# harp_input_expander.net
KiCad netlist of a schematic drawn in EAGLE
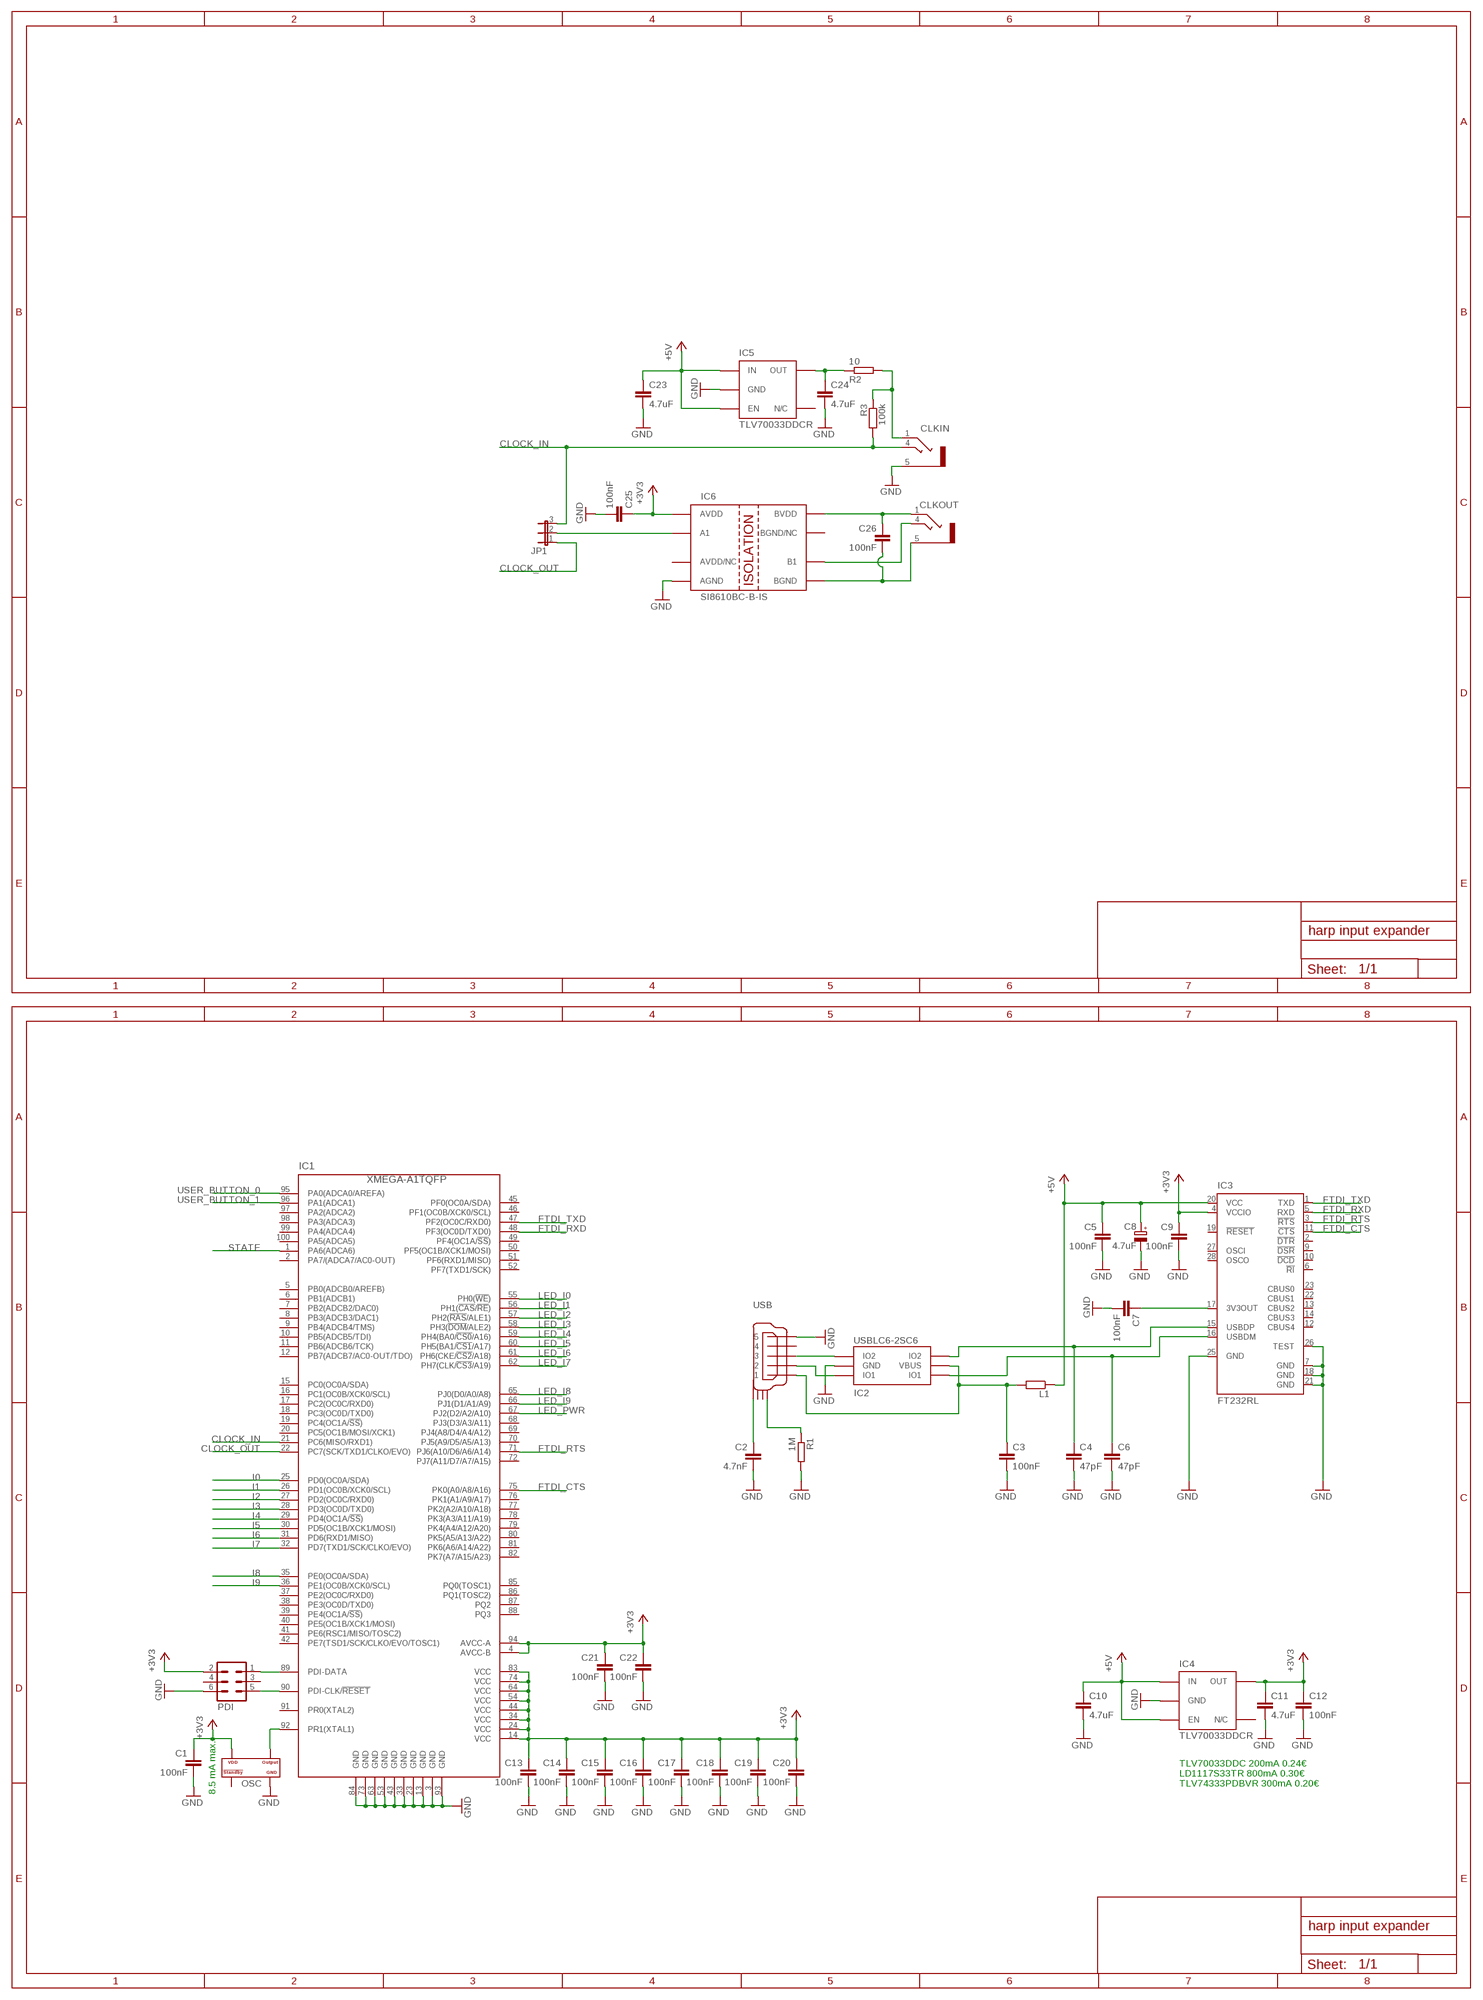
[diagram p0: schematic, sheet 1, part 1 of 2]
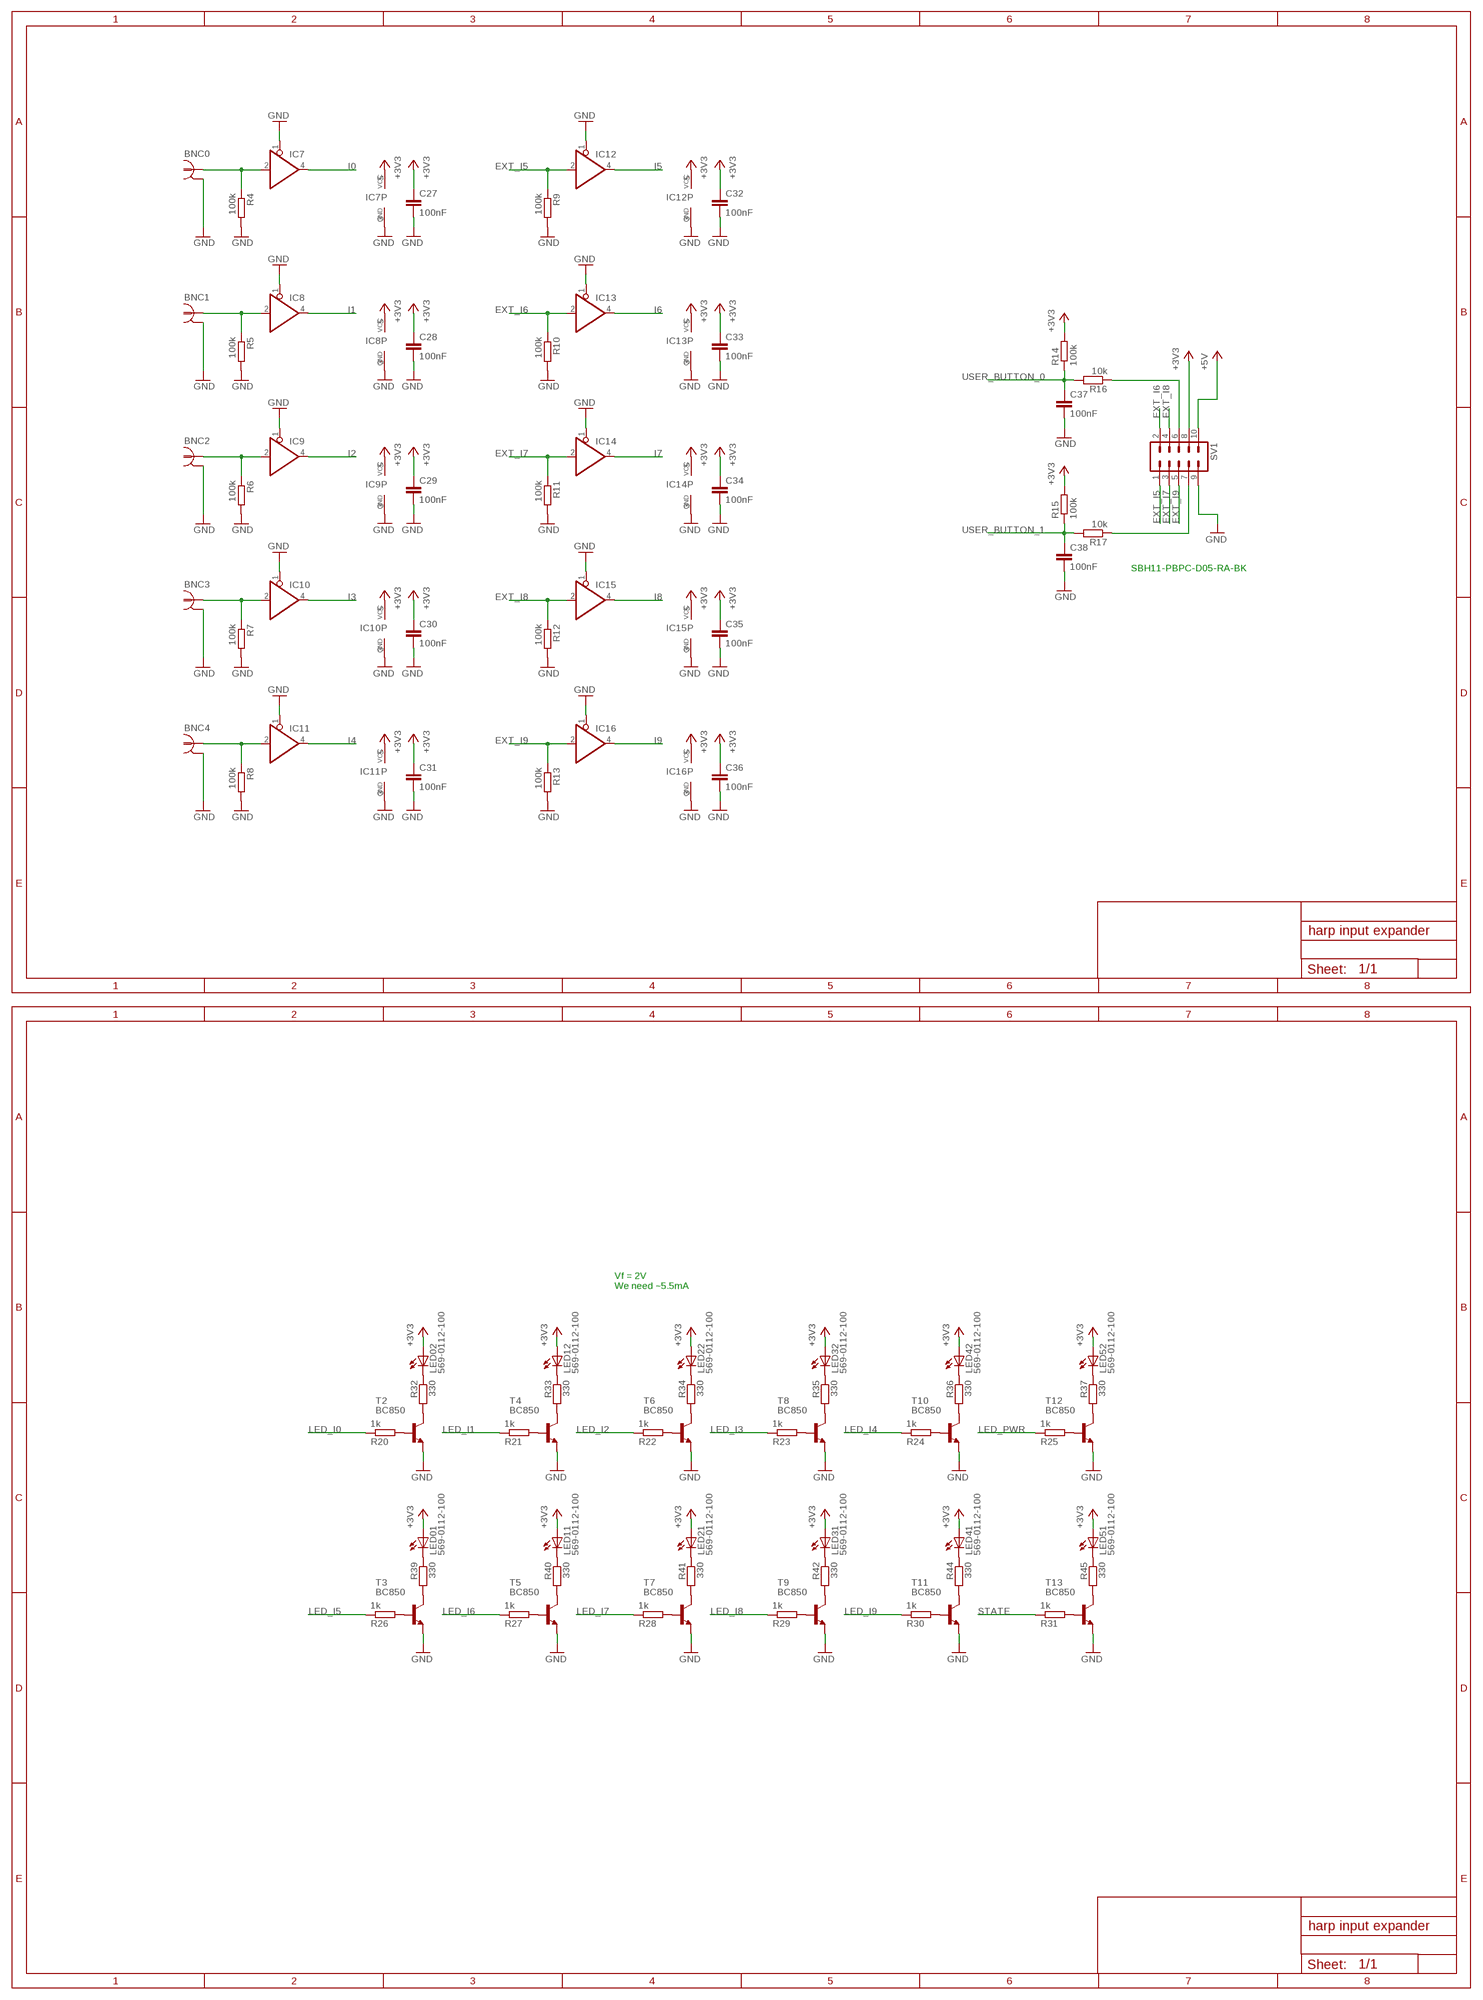
[diagram p1: schematic, sheet 1, part 2 of 2]

(export (version "E")
  (design (tool "Eeschema 10.0.6"))
  (components
    (comp (ref "BNC0")
      (value "BNC_0731000105")
      (footprint "eagle-import:0731000105")
      (libsource (lib "eagle-import") (part "BNC_0731000105"))
    )
    (comp (ref "BNC1")
      (value "BNC_0731000105")
      (footprint "eagle-import:0731000105")
      (libsource (lib "eagle-import") (part "BNC_0731000105"))
    )
    (comp (ref "BNC2")
      (value "BNC_0731000105")
      (footprint "eagle-import:0731000105")
      (libsource (lib "eagle-import") (part "BNC_0731000105"))
    )
    (comp (ref "BNC3")
      (value "BNC_0731000105")
      (footprint "eagle-import:0731000105")
      (libsource (lib "eagle-import") (part "BNC_0731000105"))
    )
    (comp (ref "BNC4")
      (value "BNC_0731000105")
      (footprint "eagle-import:0731000105")
      (libsource (lib "eagle-import") (part "BNC_0731000105"))
    )
    (comp (ref "C1")
      (value "100nF")
      (footprint "eagle-import:C0402")
      (libsource (lib "eagle-import") (part "C-EUC0402"))
    )
    (comp (ref "C2")
      (value "4.7nF")
      (footprint "eagle-import:C0402")
      (libsource (lib "eagle-import") (part "C-EUC0402"))
    )
    (comp (ref "C3")
      (value "100nF")
      (footprint "eagle-import:C0402")
      (libsource (lib "eagle-import") (part "C-EUC0402"))
    )
    (comp (ref "C4")
      (value "47pF")
      (footprint "eagle-import:C0402")
      (libsource (lib "eagle-import") (part "C-EUC0402"))
    )
    (comp (ref "C5")
      (value "100nF")
      (footprint "eagle-import:C0402")
      (libsource (lib "eagle-import") (part "C-EUC0402"))
    )
    (comp (ref "C6")
      (value "47pF")
      (footprint "eagle-import:C0402")
      (libsource (lib "eagle-import") (part "C-EUC0402"))
    )
    (comp (ref "C7")
      (value "100nF")
      (footprint "eagle-import:C0402")
      (libsource (lib "eagle-import") (part "C-EUC0402"))
    )
    (comp (ref "C8")
      (value "4.7uF")
      (footprint "eagle-import:A_3216-18W")
      (libsource (lib "eagle-import") (part "CPOL-EUA/3216-18W"))
    )
    (comp (ref "C9")
      (value "100nF")
      (footprint "eagle-import:C0402")
      (libsource (lib "eagle-import") (part "C-EUC0402"))
    )
    (comp (ref "C10")
      (value "4.7uF")
      (footprint "eagle-import:C0603")
      (libsource (lib "eagle-import") (part "C-EUC0603"))
    )
    (comp (ref "C11")
      (value "4.7uF")
      (footprint "eagle-import:C0603")
      (libsource (lib "eagle-import") (part "C-EUC0603"))
    )
    (comp (ref "C12")
      (value "100nF")
      (footprint "eagle-import:C0402")
      (libsource (lib "eagle-import") (part "C-EUC0402"))
    )
    (comp (ref "C13")
      (value "100nF")
      (footprint "eagle-import:C0402")
      (libsource (lib "eagle-import") (part "C-EUC0402"))
    )
    (comp (ref "C14")
      (value "100nF")
      (footprint "eagle-import:C0402")
      (libsource (lib "eagle-import") (part "C-EUC0402"))
    )
    (comp (ref "C15")
      (value "100nF")
      (footprint "eagle-import:C0402")
      (libsource (lib "eagle-import") (part "C-EUC0402"))
    )
    (comp (ref "C16")
      (value "100nF")
      (footprint "eagle-import:C0402")
      (libsource (lib "eagle-import") (part "C-EUC0402"))
    )
    (comp (ref "C17")
      (value "100nF")
      (footprint "eagle-import:C0402")
      (libsource (lib "eagle-import") (part "C-EUC0402"))
    )
    (comp (ref "C18")
      (value "100nF")
      (footprint "eagle-import:C0402")
      (libsource (lib "eagle-import") (part "C-EUC0402"))
    )
    (comp (ref "C19")
      (value "100nF")
      (footprint "eagle-import:C0402")
      (libsource (lib "eagle-import") (part "C-EUC0402"))
    )
    (comp (ref "C20")
      (value "100nF")
      (footprint "eagle-import:C0402")
      (libsource (lib "eagle-import") (part "C-EUC0402"))
    )
    (comp (ref "C21")
      (value "100nF")
      (footprint "eagle-import:C0402")
      (libsource (lib "eagle-import") (part "C-EUC0402"))
    )
    (comp (ref "C22")
      (value "100nF")
      (footprint "eagle-import:C0402")
      (libsource (lib "eagle-import") (part "C-EUC0402"))
    )
    (comp (ref "C23")
      (value "4.7uF")
      (footprint "eagle-import:C0603")
      (libsource (lib "eagle-import") (part "C-EUC0603"))
    )
    (comp (ref "C24")
      (value "4.7uF")
      (footprint "eagle-import:C0603")
      (libsource (lib "eagle-import") (part "C-EUC0603"))
    )
    (comp (ref "C25")
      (value "100nF")
      (footprint "eagle-import:C0402")
      (libsource (lib "eagle-import") (part "C-EUC0402"))
    )
    (comp (ref "C26")
      (value "100nF")
      (footprint "eagle-import:C0402")
      (libsource (lib "eagle-import") (part "C-EUC0402"))
    )
    (comp (ref "C27")
      (value "100nF")
      (footprint "eagle-import:C0402")
      (libsource (lib "eagle-import") (part "C-EUC0402"))
    )
    (comp (ref "C28")
      (value "100nF")
      (footprint "eagle-import:C0402")
      (libsource (lib "eagle-import") (part "C-EUC0402"))
    )
    (comp (ref "C29")
      (value "100nF")
      (footprint "eagle-import:C0402")
      (libsource (lib "eagle-import") (part "C-EUC0402"))
    )
    (comp (ref "C30")
      (value "100nF")
      (footprint "eagle-import:C0402")
      (libsource (lib "eagle-import") (part "C-EUC0402"))
    )
    (comp (ref "C31")
      (value "100nF")
      (footprint "eagle-import:C0402")
      (libsource (lib "eagle-import") (part "C-EUC0402"))
    )
    (comp (ref "C32")
      (value "100nF")
      (footprint "eagle-import:C0402")
      (libsource (lib "eagle-import") (part "C-EUC0402"))
    )
    (comp (ref "C33")
      (value "100nF")
      (footprint "eagle-import:C0402")
      (libsource (lib "eagle-import") (part "C-EUC0402"))
    )
    (comp (ref "C34")
      (value "100nF")
      (footprint "eagle-import:C0402")
      (libsource (lib "eagle-import") (part "C-EUC0402"))
    )
    (comp (ref "C35")
      (value "100nF")
      (footprint "eagle-import:C0402")
      (libsource (lib "eagle-import") (part "C-EUC0402"))
    )
    (comp (ref "C36")
      (value "100nF")
      (footprint "eagle-import:C0402")
      (libsource (lib "eagle-import") (part "C-EUC0402"))
    )
    (comp (ref "C37")
      (value "100nF")
      (footprint "eagle-import:C0402")
      (libsource (lib "eagle-import") (part "C-EUC0402"))
    )
    (comp (ref "C38")
      (value "100nF")
      (footprint "eagle-import:C0402")
      (libsource (lib "eagle-import") (part "C-EUC0402"))
    )
    (comp (ref "CLKIN")
      (value "STEREO_JACK")
      (footprint "eagle-import:35RASMT2BHNTRX")
      (libsource (lib "eagle-import") (part "STEREO_JACK"))
    )
    (comp (ref "CLKOUT")
      (value "STEREO_JACK")
      (footprint "eagle-import:35RASMT2BHNTRX")
      (libsource (lib "eagle-import") (part "STEREO_JACK"))
    )
    (comp (ref "IC1")
      (value "XMEGA-A1TQFP")
      (footprint "eagle-import:TQFP100")
      (libsource (lib "eagle-import") (part "XMEGA-A1TQFP"))
    )
    (comp (ref "IC2")
      (value "USBLC6-2SC6")
      (footprint "eagle-import:SOT23-6L")
      (libsource (lib "eagle-import") (part "USBLC6-2"))
    )
    (comp (ref "IC3")
      (value "FT232RL")
      (footprint "eagle-import:SSOP28")
      (libsource (lib "eagle-import") (part "FT232RL"))
    )
    (comp (ref "IC4")
      (value "TLV70033DDCR")
      (footprint "eagle-import:TSOT23-5")
      (libsource (lib "eagle-import") (part "TLV700XX"))
    )
    (comp (ref "IC5")
      (value "TLV70033DDCR")
      (footprint "eagle-import:TSOT23-5")
      (libsource (lib "eagle-import") (part "TLV700XX"))
    )
    (comp (ref "IC6")
      (value "SI8610BC-B-IS")
      (footprint "eagle-import:SO-08")
      (libsource (lib "eagle-import") (part "SI8610"))
    )
    (comp (ref "IC7")
      (value "74AHC1G125DBV")
      (footprint "eagle-import:SOT23-5")
      (libsource (lib "eagle-import") (part "741G125DBVAHC"))
    )
    (comp (ref "IC8")
      (value "74AHC1G125DBV")
      (footprint "eagle-import:SOT23-5")
      (libsource (lib "eagle-import") (part "741G125DBVAHC"))
    )
    (comp (ref "IC9")
      (value "74AHC1G125DBV")
      (footprint "eagle-import:SOT23-5")
      (libsource (lib "eagle-import") (part "741G125DBVAHC"))
    )
    (comp (ref "IC10")
      (value "74AHC1G125DBV")
      (footprint "eagle-import:SOT23-5")
      (libsource (lib "eagle-import") (part "741G125DBVAHC"))
    )
    (comp (ref "IC11")
      (value "74AHC1G125DBV")
      (footprint "eagle-import:SOT23-5")
      (libsource (lib "eagle-import") (part "741G125DBVAHC"))
    )
    (comp (ref "IC12")
      (value "74AHC1G125DBV")
      (footprint "eagle-import:SOT23-5")
      (libsource (lib "eagle-import") (part "741G125DBVAHC"))
    )
    (comp (ref "IC13")
      (value "74AHC1G125DBV")
      (footprint "eagle-import:SOT23-5")
      (libsource (lib "eagle-import") (part "741G125DBVAHC"))
    )
    (comp (ref "IC14")
      (value "74AHC1G125DBV")
      (footprint "eagle-import:SOT23-5")
      (libsource (lib "eagle-import") (part "741G125DBVAHC"))
    )
    (comp (ref "IC15")
      (value "74AHC1G125DBV")
      (footprint "eagle-import:SOT23-5")
      (libsource (lib "eagle-import") (part "741G125DBVAHC"))
    )
    (comp (ref "IC16")
      (value "74AHC1G125DBV")
      (footprint "eagle-import:SOT23-5")
      (libsource (lib "eagle-import") (part "741G125DBVAHC"))
    )
    (comp (ref "JP1")
      (value "JP2E")
      (footprint "eagle-import:JP2")
      (libsource (lib "eagle-import") (part "JP2E"))
    )
    (comp (ref "L1")
      (value "???")
      (footprint "eagle-import:R0805")
      (libsource (lib "eagle-import") (part "R-EU_R0805"))
    )
    (comp (ref "LED0")
      (value "569-0112-100")
      (footprint "eagle-import:569-011X-X00_LED_ARRAY")
      (libsource (lib "eagle-import") (part "LED_2X_VERTICAL"))
    )
    (comp (ref "LED1")
      (value "569-0112-100")
      (footprint "eagle-import:569-011X-X00_LED_ARRAY")
      (libsource (lib "eagle-import") (part "LED_2X_VERTICAL"))
    )
    (comp (ref "LED2")
      (value "569-0112-100")
      (footprint "eagle-import:569-011X-X00_LED_ARRAY")
      (libsource (lib "eagle-import") (part "LED_2X_VERTICAL"))
    )
    (comp (ref "LED3")
      (value "569-0112-100")
      (footprint "eagle-import:569-011X-X00_LED_ARRAY")
      (libsource (lib "eagle-import") (part "LED_2X_VERTICAL"))
    )
    (comp (ref "LED4")
      (value "569-0112-100")
      (footprint "eagle-import:569-011X-X00_LED_ARRAY")
      (libsource (lib "eagle-import") (part "LED_2X_VERTICAL"))
    )
    (comp (ref "LED5")
      (value "569-0112-100")
      (footprint "eagle-import:569-011X-X00_LED_ARRAY")
      (libsource (lib "eagle-import") (part "LED_2X_VERTICAL"))
    )
    (comp (ref "OSC")
      (value "OSCILLATOR")
      (footprint "eagle-import:OSCILLATOR_3.2X2.5")
      (libsource (lib "eagle-import") (part "OSCILLATOR"))
    )
    (comp (ref "PDI")
      (value "MA03-2")
      (footprint "eagle-import:MA03-2")
      (libsource (lib "eagle-import") (part "MA03-2"))
    )
    (comp (ref "R1")
      (value "1M")
      (footprint "eagle-import:R0402")
      (libsource (lib "eagle-import") (part "R-EU_R0402"))
    )
    (comp (ref "R2")
      (value "10")
      (footprint "eagle-import:R0402")
      (libsource (lib "eagle-import") (part "R-EU_R0402"))
    )
    (comp (ref "R3")
      (value "100k")
      (footprint "eagle-import:R0402")
      (libsource (lib "eagle-import") (part "R-EU_R0402"))
    )
    (comp (ref "R4")
      (value "100k")
      (footprint "eagle-import:R0402")
      (libsource (lib "eagle-import") (part "R-EU_R0402"))
    )
    (comp (ref "R5")
      (value "100k")
      (footprint "eagle-import:R0402")
      (libsource (lib "eagle-import") (part "R-EU_R0402"))
    )
    (comp (ref "R6")
      (value "100k")
      (footprint "eagle-import:R0402")
      (libsource (lib "eagle-import") (part "R-EU_R0402"))
    )
    (comp (ref "R7")
      (value "100k")
      (footprint "eagle-import:R0402")
      (libsource (lib "eagle-import") (part "R-EU_R0402"))
    )
    (comp (ref "R8")
      (value "100k")
      (footprint "eagle-import:R0402")
      (libsource (lib "eagle-import") (part "R-EU_R0402"))
    )
    (comp (ref "R9")
      (value "100k")
      (footprint "eagle-import:R0402")
      (libsource (lib "eagle-import") (part "R-EU_R0402"))
    )
    (comp (ref "R10")
      (value "100k")
      (footprint "eagle-import:R0402")
      (libsource (lib "eagle-import") (part "R-EU_R0402"))
    )
    (comp (ref "R11")
      (value "100k")
      (footprint "eagle-import:R0402")
      (libsource (lib "eagle-import") (part "R-EU_R0402"))
    )
    (comp (ref "R12")
      (value "100k")
      (footprint "eagle-import:R0402")
      (libsource (lib "eagle-import") (part "R-EU_R0402"))
    )
    (comp (ref "R13")
      (value "100k")
      (footprint "eagle-import:R0402")
      (libsource (lib "eagle-import") (part "R-EU_R0402"))
    )
    (comp (ref "R14")
      (value "100k")
      (footprint "eagle-import:R0402")
      (libsource (lib "eagle-import") (part "R-EU_R0402"))
    )
    (comp (ref "R15")
      (value "100k")
      (footprint "eagle-import:R0402")
      (libsource (lib "eagle-import") (part "R-EU_R0402"))
    )
    (comp (ref "R16")
      (value "10k")
      (footprint "eagle-import:R0402")
      (libsource (lib "eagle-import") (part "R-EU_R0402"))
    )
    (comp (ref "R17")
      (value "10k")
      (footprint "eagle-import:R0402")
      (libsource (lib "eagle-import") (part "R-EU_R0402"))
    )
    (comp (ref "R20")
      (value "1k")
      (footprint "eagle-import:R0402")
      (libsource (lib "eagle-import") (part "R-EU_R0402"))
    )
    (comp (ref "R21")
      (value "1k")
      (footprint "eagle-import:R0402")
      (libsource (lib "eagle-import") (part "R-EU_R0402"))
    )
    (comp (ref "R22")
      (value "1k")
      (footprint "eagle-import:R0402")
      (libsource (lib "eagle-import") (part "R-EU_R0402"))
    )
    (comp (ref "R23")
      (value "1k")
      (footprint "eagle-import:R0402")
      (libsource (lib "eagle-import") (part "R-EU_R0402"))
    )
    (comp (ref "R24")
      (value "1k")
      (footprint "eagle-import:R0402")
      (libsource (lib "eagle-import") (part "R-EU_R0402"))
    )
    (comp (ref "R25")
      (value "1k")
      (footprint "eagle-import:R0402")
      (libsource (lib "eagle-import") (part "R-EU_R0402"))
    )
    (comp (ref "R26")
      (value "1k")
      (footprint "eagle-import:R0402")
      (libsource (lib "eagle-import") (part "R-EU_R0402"))
    )
    (comp (ref "R27")
      (value "1k")
      (footprint "eagle-import:R0402")
      (libsource (lib "eagle-import") (part "R-EU_R0402"))
    )
    (comp (ref "R28")
      (value "1k")
      (footprint "eagle-import:R0402")
      (libsource (lib "eagle-import") (part "R-EU_R0402"))
    )
    (comp (ref "R29")
      (value "1k")
      (footprint "eagle-import:R0402")
      (libsource (lib "eagle-import") (part "R-EU_R0402"))
    )
    (comp (ref "R30")
      (value "1k")
      (footprint "eagle-import:R0402")
      (libsource (lib "eagle-import") (part "R-EU_R0402"))
    )
    (comp (ref "R31")
      (value "1k")
      (footprint "eagle-import:R0402")
      (libsource (lib "eagle-import") (part "R-EU_R0402"))
    )
    (comp (ref "R32")
      (value "330")
      (footprint "eagle-import:R0402")
      (libsource (lib "eagle-import") (part "R-EU_R0402"))
    )
    (comp (ref "R33")
      (value "330")
      (footprint "eagle-import:R0402")
      (libsource (lib "eagle-import") (part "R-EU_R0402"))
    )
    (comp (ref "R34")
      (value "330")
      (footprint "eagle-import:R0402")
      (libsource (lib "eagle-import") (part "R-EU_R0402"))
    )
    (comp (ref "R35")
      (value "330")
      (footprint "eagle-import:R0402")
      (libsource (lib "eagle-import") (part "R-EU_R0402"))
    )
    (comp (ref "R36")
      (value "330")
      (footprint "eagle-import:R0402")
      (libsource (lib "eagle-import") (part "R-EU_R0402"))
    )
    (comp (ref "R37")
      (value "330")
      (footprint "eagle-import:R0402")
      (libsource (lib "eagle-import") (part "R-EU_R0402"))
    )
    (comp (ref "R39")
      (value "330")
      (footprint "eagle-import:R0402")
      (libsource (lib "eagle-import") (part "R-EU_R0402"))
    )
    (comp (ref "R40")
      (value "330")
      (footprint "eagle-import:R0402")
      (libsource (lib "eagle-import") (part "R-EU_R0402"))
    )
    (comp (ref "R41")
      (value "330")
      (footprint "eagle-import:R0402")
      (libsource (lib "eagle-import") (part "R-EU_R0402"))
    )
    (comp (ref "R42")
      (value "330")
      (footprint "eagle-import:R0402")
      (libsource (lib "eagle-import") (part "R-EU_R0402"))
    )
    (comp (ref "R44")
      (value "330")
      (footprint "eagle-import:R0402")
      (libsource (lib "eagle-import") (part "R-EU_R0402"))
    )
    (comp (ref "R45")
      (value "330")
      (footprint "eagle-import:R0402")
      (libsource (lib "eagle-import") (part "R-EU_R0402"))
    )
    (comp (ref "SV1")
      (value "ML10L")
      (footprint "eagle-import:ML10L")
      (libsource (lib "eagle-import") (part "ML10L"))
    )
    (comp (ref "T2")
      (value "BC850")
      (footprint "eagle-import:SOT23")
      (libsource (lib "eagle-import") (part "BC850"))
    )
    (comp (ref "T3")
      (value "BC850")
      (footprint "eagle-import:SOT23")
      (libsource (lib "eagle-import") (part "BC850"))
    )
    (comp (ref "T4")
      (value "BC850")
      (footprint "eagle-import:SOT23")
      (libsource (lib "eagle-import") (part "BC850"))
    )
    (comp (ref "T5")
      (value "BC850")
      (footprint "eagle-import:SOT23")
      (libsource (lib "eagle-import") (part "BC850"))
    )
    (comp (ref "T6")
      (value "BC850")
      (footprint "eagle-import:SOT23")
      (libsource (lib "eagle-import") (part "BC850"))
    )
    (comp (ref "T7")
      (value "BC850")
      (footprint "eagle-import:SOT23")
      (libsource (lib "eagle-import") (part "BC850"))
    )
    (comp (ref "T8")
      (value "BC850")
      (footprint "eagle-import:SOT23")
      (libsource (lib "eagle-import") (part "BC850"))
    )
    (comp (ref "T9")
      (value "BC850")
      (footprint "eagle-import:SOT23")
      (libsource (lib "eagle-import") (part "BC850"))
    )
    (comp (ref "T10")
      (value "BC850")
      (footprint "eagle-import:SOT23")
      (libsource (lib "eagle-import") (part "BC850"))
    )
    (comp (ref "T11")
      (value "BC850")
      (footprint "eagle-import:SOT23")
      (libsource (lib "eagle-import") (part "BC850"))
    )
    (comp (ref "T12")
      (value "BC850")
      (footprint "eagle-import:SOT23")
      (libsource (lib "eagle-import") (part "BC850"))
    )
    (comp (ref "T13")
      (value "BC850")
      (footprint "eagle-import:SOT23")
      (libsource (lib "eagle-import") (part "BC850"))
    )
    (comp (ref "USB")
      (value "USB_MINI_B")
      (footprint "eagle-import:240-0002-1")
      (libsource (lib "eagle-import") (part "USB_MINI_B"))
    )
  )
  (nets
    (net (code "1") (name "+3V3") (class "Default")
      (node (ref "C1") (pin "1") (pinfunction "1_1") (pintype "passive"))
      (node (ref "C11") (pin "1") (pinfunction "1_1") (pintype "passive"))
      (node (ref "C12") (pin "1") (pinfunction "1_1") (pintype "passive"))
      (node (ref "C13") (pin "1") (pinfunction "1_1") (pintype "passive"))
      (node (ref "C14") (pin "1") (pinfunction "1_1") (pintype "passive"))
      (node (ref "C15") (pin "1") (pinfunction "1_1") (pintype "passive"))
      (node (ref "C16") (pin "1") (pinfunction "1_1") (pintype "passive"))
      (node (ref "C17") (pin "1") (pinfunction "1_1") (pintype "passive"))
      (node (ref "C18") (pin "1") (pinfunction "1_1") (pintype "passive"))
      (node (ref "C19") (pin "1") (pinfunction "1_1") (pintype "passive"))
      (node (ref "C20") (pin "1") (pinfunction "1_1") (pintype "passive"))
      (node (ref "C21") (pin "1") (pinfunction "1_1") (pintype "passive"))
      (node (ref "C22") (pin "1") (pinfunction "1_1") (pintype "passive"))
      (node (ref "C25") (pin "1") (pinfunction "1_1") (pintype "passive"))
      (node (ref "C27") (pin "1") (pinfunction "1_1") (pintype "passive"))
      (node (ref "C28") (pin "1") (pinfunction "1_1") (pintype "passive"))
      (node (ref "C29") (pin "1") (pinfunction "1_1") (pintype "passive"))
      (node (ref "C30") (pin "1") (pinfunction "1_1") (pintype "passive"))
      (node (ref "C31") (pin "1") (pinfunction "1_1") (pintype "passive"))
      (node (ref "C32") (pin "1") (pinfunction "1_1") (pintype "passive"))
      (node (ref "C33") (pin "1") (pinfunction "1_1") (pintype "passive"))
      (node (ref "C34") (pin "1") (pinfunction "1_1") (pintype "passive"))
      (node (ref "C35") (pin "1") (pinfunction "1_1") (pintype "passive"))
      (node (ref "C36") (pin "1") (pinfunction "1_1") (pintype "passive"))
      (node (ref "C9") (pin "1") (pinfunction "1_1") (pintype "passive"))
      (node (ref "IC1") (pin "14") (pinfunction "VCC_14") (pintype "power_in"))
      (node (ref "IC1") (pin "24") (pinfunction "VCC_24") (pintype "power_in"))
      (node (ref "IC1") (pin "34") (pinfunction "VCC_34") (pintype "power_in"))
      (node (ref "IC1") (pin "4") (pinfunction "AVCC-B_4") (pintype "power_in"))
      (node (ref "IC1") (pin "44") (pinfunction "VCC_44") (pintype "power_in"))
      (node (ref "IC1") (pin "54") (pinfunction "VCC_54") (pintype "power_in"))
      (node (ref "IC1") (pin "64") (pinfunction "VCC_64") (pintype "power_in"))
      (node (ref "IC1") (pin "74") (pinfunction "VCC_74") (pintype "power_in"))
      (node (ref "IC1") (pin "83") (pinfunction "VCC_83") (pintype "power_in"))
      (node (ref "IC1") (pin "94") (pinfunction "AVCC-A_94") (pintype "power_in"))
      (node (ref "IC10") (pin "5") (pinfunction "VCC_5") (pintype "power_in"))
      (node (ref "IC11") (pin "5") (pinfunction "VCC_5") (pintype "power_in"))
      (node (ref "IC12") (pin "5") (pinfunction "VCC_5") (pintype "power_in"))
      (node (ref "IC13") (pin "5") (pinfunction "VCC_5") (pintype "power_in"))
      (node (ref "IC14") (pin "5") (pinfunction "VCC_5") (pintype "power_in"))
      (node (ref "IC15") (pin "5") (pinfunction "VCC_5") (pintype "power_in"))
      (node (ref "IC16") (pin "5") (pinfunction "VCC_5") (pintype "power_in"))
      (node (ref "IC3") (pin "4") (pinfunction "VCCIO_4") (pintype "power_in"))
      (node (ref "IC4") (pin "5") (pinfunction "OUT_5") (pintype "bidirectional"))
      (node (ref "IC6") (pin "1") (pinfunction "AVDD_1") (pintype "bidirectional"))
      (node (ref "IC7") (pin "5") (pinfunction "VCC_5") (pintype "power_in"))
      (node (ref "IC8") (pin "5") (pinfunction "VCC_5") (pintype "power_in"))
      (node (ref "IC9") (pin "5") (pinfunction "VCC_5") (pintype "power_in"))
      (node (ref "LED0") (pin "A1") (pinfunction "A_A1") (pintype "passive"))
      (node (ref "LED0") (pin "A2") (pinfunction "A_A2") (pintype "passive"))
      (node (ref "LED1") (pin "A1") (pinfunction "A_A1") (pintype "passive"))
      (node (ref "LED1") (pin "A2") (pinfunction "A_A2") (pintype "passive"))
      (node (ref "LED2") (pin "A1") (pinfunction "A_A1") (pintype "passive"))
      (node (ref "LED2") (pin "A2") (pinfunction "A_A2") (pintype "passive"))
      (node (ref "LED3") (pin "A1") (pinfunction "A_A1") (pintype "passive"))
      (node (ref "LED3") (pin "A2") (pinfunction "A_A2") (pintype "passive"))
      (node (ref "LED4") (pin "A1") (pinfunction "A_A1") (pintype "passive"))
      (node (ref "LED4") (pin "A2") (pinfunction "A_A2") (pintype "passive"))
      (node (ref "LED5") (pin "A1") (pinfunction "A_A1") (pintype "passive"))
      (node (ref "LED5") (pin "A2") (pinfunction "A_A2") (pintype "passive"))
      (node (ref "OSC") (pin "P$4") (pinfunction "VDD_P$4") (pintype "passive"))
      (node (ref "PDI") (pin "2") (pinfunction "2_2") (pintype "passive"))
      (node (ref "R14") (pin "2") (pinfunction "2_2") (pintype "passive"))
      (node (ref "R15") (pin "2") (pinfunction "2_2") (pintype "passive"))
      (node (ref "SV1") (pin "8") (pinfunction "8_8") (pintype "passive"))
    )
    (net (code "2") (name "+5V") (class "Default")
      (node (ref "C10") (pin "1") (pinfunction "1_1") (pintype "passive"))
      (node (ref "C23") (pin "1") (pinfunction "1_1") (pintype "passive"))
      (node (ref "C5") (pin "1") (pinfunction "1_1") (pintype "passive"))
      (node (ref "C8") (pin "+") (pinfunction "+_+") (pintype "passive"))
      (node (ref "IC3") (pin "20") (pinfunction "VCC_20") (pintype "power_in"))
      (node (ref "IC4") (pin "1") (pinfunction "IN_1") (pintype "bidirectional"))
      (node (ref "IC4") (pin "3") (pinfunction "EN_3") (pintype "bidirectional"))
      (node (ref "IC5") (pin "1") (pinfunction "IN_1") (pintype "bidirectional"))
      (node (ref "IC5") (pin "3") (pinfunction "EN_3") (pintype "bidirectional"))
      (node (ref "L1") (pin "1") (pinfunction "1_1") (pintype "passive"))
      (node (ref "SV1") (pin "10") (pinfunction "10_10") (pintype "passive"))
    )
    (net (code "3") (name "/CLOCK_IN") (class "Default")
      (node (ref "CLKIN") (pin "4") (pinfunction "4_4") (pintype "passive"))
      (node (ref "IC1") (pin "21") (pinfunction "PC6(MISO/RXD1)_21") (pintype "bidirectional"))
      (node (ref "JP1") (pin "3") (pinfunction "3_3") (pintype "passive"))
      (node (ref "R3") (pin "2") (pinfunction "2_2") (pintype "passive"))
    )
    (net (code "4") (name "/CLOCK_OUT") (class "Default")
      (node (ref "IC1") (pin "22") (pinfunction "PC7(SCK/TXD1/CLKO/EVO)_22") (pintype "bidirectional"))
      (node (ref "JP1") (pin "1") (pinfunction "1_1") (pintype "passive"))
    )
    (net (code "5") (name "/EXT_I5") (class "Default")
      (node (ref "IC12") (pin "2") (pinfunction "I_2") (pintype "input"))
      (node (ref "R9") (pin "1") (pinfunction "1_1") (pintype "passive"))
      (node (ref "SV1") (pin "1") (pinfunction "1_1") (pintype "passive"))
    )
    (net (code "6") (name "/EXT_I6") (class "Default")
      (node (ref "IC13") (pin "2") (pinfunction "I_2") (pintype "input"))
      (node (ref "R10") (pin "1") (pinfunction "1_1") (pintype "passive"))
      (node (ref "SV1") (pin "2") (pinfunction "2_2") (pintype "passive"))
    )
    (net (code "7") (name "/EXT_I7") (class "Default")
      (node (ref "IC14") (pin "2") (pinfunction "I_2") (pintype "input"))
      (node (ref "R11") (pin "1") (pinfunction "1_1") (pintype "passive"))
      (node (ref "SV1") (pin "3") (pinfunction "3_3") (pintype "passive"))
    )
    (net (code "8") (name "/EXT_I8") (class "Default")
      (node (ref "IC15") (pin "2") (pinfunction "I_2") (pintype "input"))
      (node (ref "R12") (pin "1") (pinfunction "1_1") (pintype "passive"))
      (node (ref "SV1") (pin "4") (pinfunction "4_4") (pintype "passive"))
    )
    (net (code "9") (name "/EXT_I9") (class "Default")
      (node (ref "IC16") (pin "2") (pinfunction "I_2") (pintype "input"))
      (node (ref "R13") (pin "1") (pinfunction "1_1") (pintype "passive"))
      (node (ref "SV1") (pin "5") (pinfunction "5_5") (pintype "passive"))
    )
    (net (code "10") (name "/FTDI_CTS") (class "Default")
      (node (ref "IC1") (pin "75") (pinfunction "PK0(A0/A8/A16)_75") (pintype "bidirectional"))
      (node (ref "IC3") (pin "11") (pinfunction "~{CTS}_11") (pintype "input"))
    )
    (net (code "11") (name "/FTDI_RTS") (class "Default")
      (node (ref "IC1") (pin "71") (pinfunction "PJ6(A10/D6/A6/A14)_71") (pintype "bidirectional"))
      (node (ref "IC3") (pin "3") (pinfunction "~{RTS}_3") (pintype "output"))
    )
    (net (code "12") (name "/FTDI_RXD") (class "Default")
      (node (ref "IC1") (pin "48") (pinfunction "PF3(OC0D/TXD0)_48") (pintype "bidirectional"))
      (node (ref "IC3") (pin "5") (pinfunction "RXD_5") (pintype "input"))
    )
    (net (code "13") (name "/FTDI_TXD") (class "Default")
      (node (ref "IC1") (pin "47") (pinfunction "PF2(OC0C/RXD0)_47") (pintype "bidirectional"))
      (node (ref "IC3") (pin "1") (pinfunction "TXD_1") (pintype "output"))
    )
    (net (code "14") (name "/I0") (class "Default")
      (node (ref "IC1") (pin "25") (pinfunction "PD0(OC0A/SDA)_25") (pintype "bidirectional"))
      (node (ref "IC7") (pin "4") (pinfunction "O_4") (pintype "tri_state"))
    )
    (net (code "15") (name "/I1") (class "Default")
      (node (ref "IC1") (pin "26") (pinfunction "PD1(OC0B/XCK0/SCL)_26") (pintype "bidirectional"))
      (node (ref "IC8") (pin "4") (pinfunction "O_4") (pintype "tri_state"))
    )
    (net (code "16") (name "/I2") (class "Default")
      (node (ref "IC1") (pin "27") (pinfunction "PD2(OC0C/RXD0)_27") (pintype "bidirectional"))
      (node (ref "IC9") (pin "4") (pinfunction "O_4") (pintype "tri_state"))
    )
    (net (code "17") (name "/I3") (class "Default")
      (node (ref "IC1") (pin "28") (pinfunction "PD3(OC0D/TXD0)_28") (pintype "bidirectional"))
      (node (ref "IC10") (pin "4") (pinfunction "O_4") (pintype "tri_state"))
    )
    (net (code "18") (name "/I4") (class "Default")
      (node (ref "IC1") (pin "29") (pinfunction "PD4(OC1A/~{SS})_29") (pintype "bidirectional"))
      (node (ref "IC11") (pin "4") (pinfunction "O_4") (pintype "tri_state"))
    )
    (net (code "19") (name "/I5") (class "Default")
      (node (ref "IC1") (pin "30") (pinfunction "PD5(OC1B/XCK1/MOSI)_30") (pintype "bidirectional"))
      (node (ref "IC12") (pin "4") (pinfunction "O_4") (pintype "tri_state"))
    )
    (net (code "20") (name "/I6") (class "Default")
      (node (ref "IC1") (pin "31") (pinfunction "PD6(RXD1/MISO)_31") (pintype "bidirectional"))
      (node (ref "IC13") (pin "4") (pinfunction "O_4") (pintype "tri_state"))
    )
    (net (code "21") (name "/I7") (class "Default")
      (node (ref "IC1") (pin "32") (pinfunction "PD7(TXD1/SCK/CLKO/EVO)_32") (pintype "bidirectional"))
      (node (ref "IC14") (pin "4") (pinfunction "O_4") (pintype "tri_state"))
    )
    (net (code "22") (name "/I8") (class "Default")
      (node (ref "IC1") (pin "35") (pinfunction "PE0(OC0A/SDA)_35") (pintype "bidirectional"))
      (node (ref "IC15") (pin "4") (pinfunction "O_4") (pintype "tri_state"))
    )
    (net (code "23") (name "/I9") (class "Default")
      (node (ref "IC1") (pin "36") (pinfunction "PE1(OC0B/XCK0/SCL)_36") (pintype "bidirectional"))
      (node (ref "IC16") (pin "4") (pinfunction "O_4") (pintype "tri_state"))
    )
    (net (code "24") (name "/LED_I0") (class "Default")
      (node (ref "IC1") (pin "55") (pinfunction "PH0(~{WE})_55") (pintype "bidirectional"))
      (node (ref "R20") (pin "1") (pinfunction "1_1") (pintype "passive"))
    )
    (net (code "25") (name "/LED_I1") (class "Default")
      (node (ref "IC1") (pin "56") (pinfunction "PH1(~{CAS}/~{RE})_56") (pintype "bidirectional"))
      (node (ref "R21") (pin "1") (pinfunction "1_1") (pintype "passive"))
    )
    (net (code "26") (name "/LED_I2") (class "Default")
      (node (ref "IC1") (pin "57") (pinfunction "PH2(~{RAS}/ALE1)_57") (pintype "bidirectional"))
      (node (ref "R22") (pin "1") (pinfunction "1_1") (pintype "passive"))
    )
    (net (code "27") (name "/LED_I3") (class "Default")
      (node (ref "IC1") (pin "58") (pinfunction "PH3(~{DOM}/ALE2)_58") (pintype "bidirectional"))
      (node (ref "R23") (pin "1") (pinfunction "1_1") (pintype "passive"))
    )
    (net (code "28") (name "/LED_I4") (class "Default")
      (node (ref "IC1") (pin "59") (pinfunction "PH4(BA0/~{CS0}/A16)_59") (pintype "bidirectional"))
      (node (ref "R24") (pin "1") (pinfunction "1_1") (pintype "passive"))
    )
    (net (code "29") (name "/LED_I5") (class "Default")
      (node (ref "IC1") (pin "60") (pinfunction "PH5(BA1/~{CS1}/A17)_60") (pintype "bidirectional"))
      (node (ref "R26") (pin "1") (pinfunction "1_1") (pintype "passive"))
    )
    (net (code "30") (name "/LED_I6") (class "Default")
      (node (ref "IC1") (pin "61") (pinfunction "PH6(CKE/~{CS2}/A18)_61") (pintype "bidirectional"))
      (node (ref "R27") (pin "1") (pinfunction "1_1") (pintype "passive"))
    )
    (net (code "31") (name "/LED_I7") (class "Default")
      (node (ref "IC1") (pin "62") (pinfunction "PH7(CLK/~{CS3}/A19)_62") (pintype "bidirectional"))
      (node (ref "R28") (pin "1") (pinfunction "1_1") (pintype "passive"))
    )
    (net (code "32") (name "/LED_I8") (class "Default")
      (node (ref "IC1") (pin "65") (pinfunction "PJ0(D0/A0/A8)_65") (pintype "bidirectional"))
      (node (ref "R29") (pin "1") (pinfunction "1_1") (pintype "passive"))
    )
    (net (code "33") (name "/LED_I9") (class "Default")
      (node (ref "IC1") (pin "66") (pinfunction "PJ1(D1/A1/A9)_66") (pintype "bidirectional"))
      (node (ref "R30") (pin "1") (pinfunction "1_1") (pintype "passive"))
    )
    (net (code "34") (name "/LED_PWR") (class "Default")
      (node (ref "IC1") (pin "67") (pinfunction "PJ2(D2/A2/A10)_67") (pintype "bidirectional"))
      (node (ref "R25") (pin "1") (pinfunction "1_1") (pintype "passive"))
    )
    (net (code "35") (name "/STATE") (class "Default")
      (node (ref "IC1") (pin "1") (pinfunction "PA6(ADCA6)_1") (pintype "bidirectional"))
      (node (ref "R31") (pin "1") (pinfunction "1_1") (pintype "passive"))
    )
    (net (code "36") (name "/USER_BUTTON_0") (class "Default")
      (node (ref "C37") (pin "1") (pinfunction "1_1") (pintype "passive"))
      (node (ref "IC1") (pin "95") (pinfunction "PA0(ADCA0/AREFA)_95") (pintype "bidirectional"))
      (node (ref "R14") (pin "1") (pinfunction "1_1") (pintype "passive"))
      (node (ref "R16") (pin "2") (pinfunction "2_2") (pintype "passive"))
    )
    (net (code "37") (name "/USER_BUTTON_1") (class "Default")
      (node (ref "C38") (pin "1") (pinfunction "1_1") (pintype "passive"))
      (node (ref "IC1") (pin "96") (pinfunction "PA1(ADCA1)_96") (pintype "bidirectional"))
      (node (ref "R15") (pin "1") (pinfunction "1_1") (pintype "passive"))
      (node (ref "R17") (pin "2") (pinfunction "2_2") (pintype "passive"))
    )
    (net (code "38") (name "GND") (class "Default")
      (node (ref "BNC0") (pin "2") (pinfunction "2_2") (pintype "passive"))
      (node (ref "BNC0") (pin "3") (pinfunction "2_3") (pintype "passive"))
      (node (ref "BNC1") (pin "2") (pinfunction "2_2") (pintype "passive"))
      (node (ref "BNC1") (pin "3") (pinfunction "2_3") (pintype "passive"))
      (node (ref "BNC2") (pin "2") (pinfunction "2_2") (pintype "passive"))
      (node (ref "BNC2") (pin "3") (pinfunction "2_3") (pintype "passive"))
      (node (ref "BNC3") (pin "2") (pinfunction "2_2") (pintype "passive"))
      (node (ref "BNC3") (pin "3") (pinfunction "2_3") (pintype "passive"))
      (node (ref "BNC4") (pin "2") (pinfunction "2_2") (pintype "passive"))
      (node (ref "BNC4") (pin "3") (pinfunction "2_3") (pintype "passive"))
      (node (ref "C1") (pin "2") (pinfunction "2_2") (pintype "passive"))
      (node (ref "C10") (pin "2") (pinfunction "2_2") (pintype "passive"))
      (node (ref "C11") (pin "2") (pinfunction "2_2") (pintype "passive"))
      (node (ref "C12") (pin "2") (pinfunction "2_2") (pintype "passive"))
      (node (ref "C13") (pin "2") (pinfunction "2_2") (pintype "passive"))
      (node (ref "C14") (pin "2") (pinfunction "2_2") (pintype "passive"))
      (node (ref "C15") (pin "2") (pinfunction "2_2") (pintype "passive"))
      (node (ref "C16") (pin "2") (pinfunction "2_2") (pintype "passive"))
      (node (ref "C17") (pin "2") (pinfunction "2_2") (pintype "passive"))
      (node (ref "C18") (pin "2") (pinfunction "2_2") (pintype "passive"))
      (node (ref "C19") (pin "2") (pinfunction "2_2") (pintype "passive"))
      (node (ref "C2") (pin "2") (pinfunction "2_2") (pintype "passive"))
      (node (ref "C20") (pin "2") (pinfunction "2_2") (pintype "passive"))
      (node (ref "C21") (pin "2") (pinfunction "2_2") (pintype "passive"))
      (node (ref "C22") (pin "2") (pinfunction "2_2") (pintype "passive"))
      (node (ref "C23") (pin "2") (pinfunction "2_2") (pintype "passive"))
      (node (ref "C24") (pin "2") (pinfunction "2_2") (pintype "passive"))
      (node (ref "C25") (pin "2") (pinfunction "2_2") (pintype "passive"))
      (node (ref "C27") (pin "2") (pinfunction "2_2") (pintype "passive"))
      (node (ref "C28") (pin "2") (pinfunction "2_2") (pintype "passive"))
      (node (ref "C29") (pin "2") (pinfunction "2_2") (pintype "passive"))
      (node (ref "C3") (pin "2") (pinfunction "2_2") (pintype "passive"))
      (node (ref "C30") (pin "2") (pinfunction "2_2") (pintype "passive"))
      (node (ref "C31") (pin "2") (pinfunction "2_2") (pintype "passive"))
      (node (ref "C32") (pin "2") (pinfunction "2_2") (pintype "passive"))
      (node (ref "C33") (pin "2") (pinfunction "2_2") (pintype "passive"))
      (node (ref "C34") (pin "2") (pinfunction "2_2") (pintype "passive"))
      (node (ref "C35") (pin "2") (pinfunction "2_2") (pintype "passive"))
      (node (ref "C36") (pin "2") (pinfunction "2_2") (pintype "passive"))
      (node (ref "C37") (pin "2") (pinfunction "2_2") (pintype "passive"))
      (node (ref "C38") (pin "2") (pinfunction "2_2") (pintype "passive"))
      (node (ref "C4") (pin "2") (pinfunction "2_2") (pintype "passive"))
      (node (ref "C5") (pin "2") (pinfunction "2_2") (pintype "passive"))
      (node (ref "C6") (pin "2") (pinfunction "2_2") (pintype "passive"))
      (node (ref "C7") (pin "2") (pinfunction "2_2") (pintype "passive"))
      (node (ref "C8") (pin "-") (pinfunction "-_-") (pintype "passive"))
      (node (ref "C9") (pin "2") (pinfunction "2_2") (pintype "passive"))
      (node (ref "CLKIN") (pin "5") (pinfunction "5_5") (pintype "passive"))
      (node (ref "IC1") (pin "13") (pinfunction "GND_13") (pintype "power_in"))
      (node (ref "IC1") (pin "23") (pinfunction "GND_23") (pintype "power_in"))
      (node (ref "IC1") (pin "3") (pinfunction "GND_3") (pintype "power_in"))
      (node (ref "IC1") (pin "33") (pinfunction "GND_33") (pintype "power_in"))
      (node (ref "IC1") (pin "43") (pinfunction "GND_43") (pintype "power_in"))
      (node (ref "IC1") (pin "53") (pinfunction "GND_53") (pintype "power_in"))
      (node (ref "IC1") (pin "63") (pinfunction "GND_63") (pintype "power_in"))
      (node (ref "IC1") (pin "73") (pinfunction "GND_73") (pintype "power_in"))
      (node (ref "IC1") (pin "84") (pinfunction "GND_84") (pintype "power_in"))
      (node (ref "IC1") (pin "93") (pinfunction "GND_93") (pintype "power_in"))
      (node (ref "IC10") (pin "1") (pinfunction "OE_1") (pintype "input"))
      (node (ref "IC10") (pin "3") (pinfunction "GND_3") (pintype "power_in"))
      (node (ref "IC11") (pin "1") (pinfunction "OE_1") (pintype "input"))
      (node (ref "IC11") (pin "3") (pinfunction "GND_3") (pintype "power_in"))
      (node (ref "IC12") (pin "1") (pinfunction "OE_1") (pintype "input"))
      (node (ref "IC12") (pin "3") (pinfunction "GND_3") (pintype "power_in"))
      (node (ref "IC13") (pin "1") (pinfunction "OE_1") (pintype "input"))
      (node (ref "IC13") (pin "3") (pinfunction "GND_3") (pintype "power_in"))
      (node (ref "IC14") (pin "1") (pinfunction "OE_1") (pintype "input"))
      (node (ref "IC14") (pin "3") (pinfunction "GND_3") (pintype "power_in"))
      (node (ref "IC15") (pin "1") (pinfunction "OE_1") (pintype "input"))
      (node (ref "IC15") (pin "3") (pinfunction "GND_3") (pintype "power_in"))
      (node (ref "IC16") (pin "1") (pinfunction "OE_1") (pintype "input"))
      (node (ref "IC16") (pin "3") (pinfunction "GND_3") (pintype "power_in"))
      (node (ref "IC2") (pin "P$2") (pinfunction "GND_P$2") (pintype "bidirectional"))
      (node (ref "IC3") (pin "18") (pinfunction "GND_18") (pintype "power_in"))
      (node (ref "IC3") (pin "21") (pinfunction "GND_21") (pintype "power_in"))
      (node (ref "IC3") (pin "25") (pinfunction "GND_25") (pintype "power_in"))
      (node (ref "IC3") (pin "26") (pinfunction "TEST_26") (pintype "input"))
      (node (ref "IC3") (pin "7") (pinfunction "GND_7") (pintype "power_in"))
      (node (ref "IC4") (pin "2") (pinfunction "GND_2") (pintype "bidirectional"))
      (node (ref "IC5") (pin "2") (pinfunction "GND_2") (pintype "bidirectional"))
      (node (ref "IC6") (pin "4") (pinfunction "AGND_4") (pintype "bidirectional"))
      (node (ref "IC7") (pin "1") (pinfunction "OE_1") (pintype "input"))
      (node (ref "IC7") (pin "3") (pinfunction "GND_3") (pintype "power_in"))
      (node (ref "IC8") (pin "1") (pinfunction "OE_1") (pintype "input"))
      (node (ref "IC8") (pin "3") (pinfunction "GND_3") (pintype "power_in"))
      (node (ref "IC9") (pin "1") (pinfunction "OE_1") (pintype "input"))
      (node (ref "IC9") (pin "3") (pinfunction "GND_3") (pintype "power_in"))
      (node (ref "OSC") (pin "P$2") (pinfunction "GND_P$2") (pintype "passive"))
      (node (ref "PDI") (pin "6") (pinfunction "6_6") (pintype "passive"))
      (node (ref "R1") (pin "2") (pinfunction "2_2") (pintype "passive"))
      (node (ref "R10") (pin "2") (pinfunction "2_2") (pintype "passive"))
      (node (ref "R11") (pin "2") (pinfunction "2_2") (pintype "passive"))
      (node (ref "R12") (pin "2") (pinfunction "2_2") (pintype "passive"))
      (node (ref "R13") (pin "2") (pinfunction "2_2") (pintype "passive"))
      (node (ref "R4") (pin "2") (pinfunction "2_2") (pintype "passive"))
      (node (ref "R5") (pin "2") (pinfunction "2_2") (pintype "passive"))
      (node (ref "R6") (pin "2") (pinfunction "2_2") (pintype "passive"))
      (node (ref "R7") (pin "2") (pinfunction "2_2") (pintype "passive"))
      (node (ref "R8") (pin "2") (pinfunction "2_2") (pintype "passive"))
      (node (ref "R9") (pin "2") (pinfunction "2_2") (pintype "passive"))
      (node (ref "SV1") (pin "9") (pinfunction "9_9") (pintype "passive"))
      (node (ref "T10") (pin "2") (pinfunction "E_2") (pintype "passive"))
      (node (ref "T11") (pin "2") (pinfunction "E_2") (pintype "passive"))
      (node (ref "T12") (pin "2") (pinfunction "E_2") (pintype "passive"))
      (node (ref "T13") (pin "2") (pinfunction "E_2") (pintype "passive"))
      (node (ref "T2") (pin "2") (pinfunction "E_2") (pintype "passive"))
      (node (ref "T3") (pin "2") (pinfunction "E_2") (pintype "passive"))
      (node (ref "T4") (pin "2") (pinfunction "E_2") (pintype "passive"))
      (node (ref "T5") (pin "2") (pinfunction "E_2") (pintype "passive"))
      (node (ref "T6") (pin "2") (pinfunction "E_2") (pintype "passive"))
      (node (ref "T7") (pin "2") (pinfunction "E_2") (pintype "passive"))
      (node (ref "T8") (pin "2") (pinfunction "E_2") (pintype "passive"))
      (node (ref "T9") (pin "2") (pinfunction "E_2") (pintype "passive"))
      (node (ref "USB") (pin "P$5") (pinfunction "5_P$5") (pintype "bidirectional"))
    )
    (net (code "39") (name "Net-(CLKIN-Pad1)") (class "Default")
      (node (ref "CLKIN") (pin "1") (pinfunction "1_1") (pintype "passive"))
      (node (ref "R2") (pin "2") (pinfunction "2_2") (pintype "passive"))
      (node (ref "R3") (pin "1") (pinfunction "1_1") (pintype "passive"))
    )
    (net (code "40") (name "Net-(IC1-PDI-CLK{slash}~{RESET})") (class "Default")
      (node (ref "IC1") (pin "90") (pinfunction "PDI-CLK/~{RESET}_90") (pintype "input"))
      (node (ref "PDI") (pin "5") (pinfunction "5_5") (pintype "passive"))
    )
    (net (code "41") (name "Net-(IC1-PDI-DATA)") (class "Default")
      (node (ref "IC1") (pin "89") (pinfunction "PDI-DATA_89") (pintype "bidirectional"))
      (node (ref "PDI") (pin "1") (pinfunction "1_1") (pintype "passive"))
    )
    (net (code "42") (name "Net-(IC1-PR1(XTAL1))") (class "Default")
      (node (ref "IC1") (pin "92") (pinfunction "PR1(XTAL1)_92") (pintype "bidirectional"))
      (node (ref "OSC") (pin "P$3") (pinfunction "OUTPUT_P$3") (pintype "passive"))
    )
    (net (code "43") (name "Net-(IC2-VBUS)") (class "Default")
      (node (ref "C3") (pin "1") (pinfunction "1_1") (pintype "passive"))
      (node (ref "IC2") (pin "P$5") (pinfunction "VBUS_P$5") (pintype "bidirectional"))
      (node (ref "L1") (pin "2") (pinfunction "2_2") (pintype "passive"))
      (node (ref "USB") (pin "P$1") (pinfunction "1_P$1") (pintype "bidirectional"))
    )
    (net (code "44") (name "Net-(IC3-3V3OUT)") (class "Default")
      (node (ref "C7") (pin "1") (pinfunction "1_1") (pintype "passive"))
      (node (ref "IC3") (pin "17") (pinfunction "3V3OUT_17") (pintype "output"))
    )
    (net (code "45") (name "Net-(IC3-USBDM)") (class "Default")
      (node (ref "C6") (pin "1") (pinfunction "1_1") (pintype "passive"))
      (node (ref "IC2") (pin "P$6") (pinfunction "IO1_P$6") (pintype "bidirectional"))
      (node (ref "IC3") (pin "16") (pinfunction "USBDM_16") (pintype "bidirectional"))
    )
    (net (code "46") (name "Net-(IC3-USBDP)") (class "Default")
      (node (ref "C4") (pin "1") (pinfunction "1_1") (pintype "passive"))
      (node (ref "IC2") (pin "P$4") (pinfunction "IO2_P$4") (pintype "bidirectional"))
      (node (ref "IC3") (pin "15") (pinfunction "USBDP_15") (pintype "bidirectional"))
    )
    (net (code "47") (name "Net-(IC5-OUT)") (class "Default")
      (node (ref "C24") (pin "1") (pinfunction "1_1") (pintype "passive"))
      (node (ref "IC5") (pin "5") (pinfunction "OUT_5") (pintype "bidirectional"))
      (node (ref "R2") (pin "1") (pinfunction "1_1") (pintype "passive"))
    )
    (net (code "48") (name "Net-(IC6-A1)") (class "Default")
      (node (ref "IC6") (pin "2") (pinfunction "A1_2") (pintype "bidirectional"))
      (node (ref "JP1") (pin "2") (pinfunction "2_2") (pintype "passive"))
    )
    (net (code "49") (name "Net-(IC6-B1)") (class "Default")
      (node (ref "CLKOUT") (pin "4") (pinfunction "4_4") (pintype "passive"))
      (node (ref "IC6") (pin "6") (pinfunction "B1_6") (pintype "bidirectional"))
    )
    (net (code "50") (name "Net-(IC6-BGND)") (class "Default")
      (node (ref "C26") (pin "2") (pinfunction "2_2") (pintype "passive"))
      (node (ref "CLKOUT") (pin "5") (pinfunction "5_5") (pintype "passive"))
      (node (ref "IC6") (pin "5") (pinfunction "BGND_5") (pintype "bidirectional"))
    )
    (net (code "51") (name "Net-(IC6-BVDD)") (class "Default")
      (node (ref "C26") (pin "1") (pinfunction "1_1") (pintype "passive"))
      (node (ref "CLKOUT") (pin "1") (pinfunction "1_1") (pintype "passive"))
      (node (ref "IC6") (pin "8") (pinfunction "BVDD_8") (pintype "bidirectional"))
    )
    (net (code "52") (name "Net-(IC7A-I)") (class "Default")
      (node (ref "BNC0") (pin "1") (pinfunction "1_1") (pintype "passive"))
      (node (ref "IC7") (pin "2") (pinfunction "I_2") (pintype "input"))
      (node (ref "R4") (pin "1") (pinfunction "1_1") (pintype "passive"))
    )
    (net (code "53") (name "Net-(IC8A-I)") (class "Default")
      (node (ref "BNC1") (pin "1") (pinfunction "1_1") (pintype "passive"))
      (node (ref "IC8") (pin "2") (pinfunction "I_2") (pintype "input"))
      (node (ref "R5") (pin "1") (pinfunction "1_1") (pintype "passive"))
    )
    (net (code "54") (name "Net-(IC9A-I)") (class "Default")
      (node (ref "BNC2") (pin "1") (pinfunction "1_1") (pintype "passive"))
      (node (ref "IC9") (pin "2") (pinfunction "I_2") (pintype "input"))
      (node (ref "R6") (pin "1") (pinfunction "1_1") (pintype "passive"))
    )
    (net (code "55") (name "Net-(IC10A-I)") (class "Default")
      (node (ref "BNC3") (pin "1") (pinfunction "1_1") (pintype "passive"))
      (node (ref "IC10") (pin "2") (pinfunction "I_2") (pintype "input"))
      (node (ref "R7") (pin "1") (pinfunction "1_1") (pintype "passive"))
    )
    (net (code "56") (name "Net-(IC11A-I)") (class "Default")
      (node (ref "BNC4") (pin "1") (pinfunction "1_1") (pintype "passive"))
      (node (ref "IC11") (pin "2") (pinfunction "I_2") (pintype "input"))
      (node (ref "R8") (pin "1") (pinfunction "1_1") (pintype "passive"))
    )
    (net (code "57") (name "Net-(LED0A-C)") (class "Default")
      (node (ref "LED0") (pin "C1") (pinfunction "C_C1") (pintype "passive"))
      (node (ref "R39") (pin "1") (pinfunction "1_1") (pintype "passive"))
    )
    (net (code "58") (name "Net-(LED0B-C)") (class "Default")
      (node (ref "LED0") (pin "C2") (pinfunction "C_C2") (pintype "passive"))
      (node (ref "R32") (pin "1") (pinfunction "1_1") (pintype "passive"))
    )
    (net (code "59") (name "Net-(LED1A-C)") (class "Default")
      (node (ref "LED1") (pin "C1") (pinfunction "C_C1") (pintype "passive"))
      (node (ref "R40") (pin "1") (pinfunction "1_1") (pintype "passive"))
    )
    (net (code "60") (name "Net-(LED1B-C)") (class "Default")
      (node (ref "LED1") (pin "C2") (pinfunction "C_C2") (pintype "passive"))
      (node (ref "R33") (pin "1") (pinfunction "1_1") (pintype "passive"))
    )
    (net (code "61") (name "Net-(LED2A-C)") (class "Default")
      (node (ref "LED2") (pin "C1") (pinfunction "C_C1") (pintype "passive"))
      (node (ref "R41") (pin "1") (pinfunction "1_1") (pintype "passive"))
    )
    (net (code "62") (name "Net-(LED2B-C)") (class "Default")
      (node (ref "LED2") (pin "C2") (pinfunction "C_C2") (pintype "passive"))
      (node (ref "R34") (pin "1") (pinfunction "1_1") (pintype "passive"))
    )
    (net (code "63") (name "Net-(LED3A-C)") (class "Default")
      (node (ref "LED3") (pin "C1") (pinfunction "C_C1") (pintype "passive"))
      (node (ref "R42") (pin "1") (pinfunction "1_1") (pintype "passive"))
    )
    (net (code "64") (name "Net-(LED3B-C)") (class "Default")
      (node (ref "LED3") (pin "C2") (pinfunction "C_C2") (pintype "passive"))
      (node (ref "R35") (pin "1") (pinfunction "1_1") (pintype "passive"))
    )
    (net (code "65") (name "Net-(LED4A-C)") (class "Default")
      (node (ref "LED4") (pin "C1") (pinfunction "C_C1") (pintype "passive"))
      (node (ref "R44") (pin "1") (pinfunction "1_1") (pintype "passive"))
    )
    (net (code "66") (name "Net-(LED4B-C)") (class "Default")
      (node (ref "LED4") (pin "C2") (pinfunction "C_C2") (pintype "passive"))
      (node (ref "R36") (pin "1") (pinfunction "1_1") (pintype "passive"))
    )
    (net (code "67") (name "Net-(LED5A-C)") (class "Default")
      (node (ref "LED5") (pin "C1") (pinfunction "C_C1") (pintype "passive"))
      (node (ref "R45") (pin "1") (pinfunction "1_1") (pintype "passive"))
    )
    (net (code "68") (name "Net-(LED5B-C)") (class "Default")
      (node (ref "LED5") (pin "C2") (pinfunction "C_C2") (pintype "passive"))
      (node (ref "R37") (pin "1") (pinfunction "1_1") (pintype "passive"))
    )
    (net (code "69") (name "Net-(R16-Pad1)") (class "Default")
      (node (ref "R16") (pin "1") (pinfunction "1_1") (pintype "passive"))
      (node (ref "SV1") (pin "6") (pinfunction "6_6") (pintype "passive"))
    )
    (net (code "70") (name "Net-(R17-Pad1)") (class "Default")
      (node (ref "R17") (pin "1") (pinfunction "1_1") (pintype "passive"))
      (node (ref "SV1") (pin "7") (pinfunction "7_7") (pintype "passive"))
    )
    (net (code "71") (name "Net-(T2-B)") (class "Default")
      (node (ref "R20") (pin "2") (pinfunction "2_2") (pintype "passive"))
      (node (ref "T2") (pin "1") (pinfunction "B_1") (pintype "passive"))
    )
    (net (code "72") (name "Net-(T2-C)") (class "Default")
      (node (ref "R32") (pin "2") (pinfunction "2_2") (pintype "passive"))
      (node (ref "T2") (pin "3") (pinfunction "C_3") (pintype "passive"))
    )
    (net (code "73") (name "Net-(T3-B)") (class "Default")
      (node (ref "R26") (pin "2") (pinfunction "2_2") (pintype "passive"))
      (node (ref "T3") (pin "1") (pinfunction "B_1") (pintype "passive"))
    )
    (net (code "74") (name "Net-(T3-C)") (class "Default")
      (node (ref "R39") (pin "2") (pinfunction "2_2") (pintype "passive"))
      (node (ref "T3") (pin "3") (pinfunction "C_3") (pintype "passive"))
    )
    (net (code "75") (name "Net-(T4-B)") (class "Default")
      (node (ref "R21") (pin "2") (pinfunction "2_2") (pintype "passive"))
      (node (ref "T4") (pin "1") (pinfunction "B_1") (pintype "passive"))
    )
    (net (code "76") (name "Net-(T4-C)") (class "Default")
      (node (ref "R33") (pin "2") (pinfunction "2_2") (pintype "passive"))
      (node (ref "T4") (pin "3") (pinfunction "C_3") (pintype "passive"))
    )
    (net (code "77") (name "Net-(T5-B)") (class "Default")
      (node (ref "R27") (pin "2") (pinfunction "2_2") (pintype "passive"))
      (node (ref "T5") (pin "1") (pinfunction "B_1") (pintype "passive"))
    )
    (net (code "78") (name "Net-(T5-C)") (class "Default")
      (node (ref "R40") (pin "2") (pinfunction "2_2") (pintype "passive"))
      (node (ref "T5") (pin "3") (pinfunction "C_3") (pintype "passive"))
    )
    (net (code "79") (name "Net-(T6-B)") (class "Default")
      (node (ref "R22") (pin "2") (pinfunction "2_2") (pintype "passive"))
      (node (ref "T6") (pin "1") (pinfunction "B_1") (pintype "passive"))
    )
    (net (code "80") (name "Net-(T6-C)") (class "Default")
      (node (ref "R34") (pin "2") (pinfunction "2_2") (pintype "passive"))
      (node (ref "T6") (pin "3") (pinfunction "C_3") (pintype "passive"))
    )
    (net (code "81") (name "Net-(T7-B)") (class "Default")
      (node (ref "R28") (pin "2") (pinfunction "2_2") (pintype "passive"))
      (node (ref "T7") (pin "1") (pinfunction "B_1") (pintype "passive"))
    )
    (net (code "82") (name "Net-(T7-C)") (class "Default")
      (node (ref "R41") (pin "2") (pinfunction "2_2") (pintype "passive"))
      (node (ref "T7") (pin "3") (pinfunction "C_3") (pintype "passive"))
    )
    (net (code "83") (name "Net-(T8-B)") (class "Default")
      (node (ref "R23") (pin "2") (pinfunction "2_2") (pintype "passive"))
      (node (ref "T8") (pin "1") (pinfunction "B_1") (pintype "passive"))
    )
    (net (code "84") (name "Net-(T8-C)") (class "Default")
      (node (ref "R35") (pin "2") (pinfunction "2_2") (pintype "passive"))
      (node (ref "T8") (pin "3") (pinfunction "C_3") (pintype "passive"))
    )
    (net (code "85") (name "Net-(T9-B)") (class "Default")
      (node (ref "R29") (pin "2") (pinfunction "2_2") (pintype "passive"))
      (node (ref "T9") (pin "1") (pinfunction "B_1") (pintype "passive"))
    )
    (net (code "86") (name "Net-(T9-C)") (class "Default")
      (node (ref "R42") (pin "2") (pinfunction "2_2") (pintype "passive"))
      (node (ref "T9") (pin "3") (pinfunction "C_3") (pintype "passive"))
    )
    (net (code "87") (name "Net-(T10-B)") (class "Default")
      (node (ref "R24") (pin "2") (pinfunction "2_2") (pintype "passive"))
      (node (ref "T10") (pin "1") (pinfunction "B_1") (pintype "passive"))
    )
    (net (code "88") (name "Net-(T10-C)") (class "Default")
      (node (ref "R36") (pin "2") (pinfunction "2_2") (pintype "passive"))
      (node (ref "T10") (pin "3") (pinfunction "C_3") (pintype "passive"))
    )
    (net (code "89") (name "Net-(T11-B)") (class "Default")
      (node (ref "R30") (pin "2") (pinfunction "2_2") (pintype "passive"))
      (node (ref "T11") (pin "1") (pinfunction "B_1") (pintype "passive"))
    )
    (net (code "90") (name "Net-(T11-C)") (class "Default")
      (node (ref "R44") (pin "2") (pinfunction "2_2") (pintype "passive"))
      (node (ref "T11") (pin "3") (pinfunction "C_3") (pintype "passive"))
    )
    (net (code "91") (name "Net-(T12-B)") (class "Default")
      (node (ref "R25") (pin "2") (pinfunction "2_2") (pintype "passive"))
      (node (ref "T12") (pin "1") (pinfunction "B_1") (pintype "passive"))
    )
    (net (code "92") (name "Net-(T12-C)") (class "Default")
      (node (ref "R37") (pin "2") (pinfunction "2_2") (pintype "passive"))
      (node (ref "T12") (pin "3") (pinfunction "C_3") (pintype "passive"))
    )
    (net (code "93") (name "Net-(T13-B)") (class "Default")
      (node (ref "R31") (pin "2") (pinfunction "2_2") (pintype "passive"))
      (node (ref "T13") (pin "1") (pinfunction "B_1") (pintype "passive"))
    )
    (net (code "94") (name "Net-(T13-C)") (class "Default")
      (node (ref "R45") (pin "2") (pinfunction "2_2") (pintype "passive"))
      (node (ref "T13") (pin "3") (pinfunction "C_3") (pintype "passive"))
    )
    (net (code "95") (name "Net-(USB-2)") (class "Default")
      (node (ref "IC2") (pin "P$1") (pinfunction "IO1_P$1") (pintype "bidirectional"))
      (node (ref "USB") (pin "P$2") (pinfunction "2_P$2") (pintype "bidirectional"))
    )
    (net (code "96") (name "Net-(USB-3)") (class "Default")
      (node (ref "IC2") (pin "P$3") (pinfunction "IO2_P$3") (pintype "bidirectional"))
      (node (ref "USB") (pin "P$3") (pinfunction "3_P$3") (pintype "bidirectional"))
    )
    (net (code "97") (name "Net-(USB-P$1)") (class "Default")
      (node (ref "R1") (pin "1") (pinfunction "1_1") (pintype "passive"))
      (node (ref "USB") (pin "SHIELD_1") (pinfunction "P$1_SHIELD_1") (pintype "bidirectional"))
    )
    (net (code "98") (name "Net-(USB-P$4)") (class "Default")
      (node (ref "C2") (pin "1") (pinfunction "1_1") (pintype "passive"))
      (node (ref "USB") (pin "SHIELD_4") (pinfunction "P$4_SHIELD_4") (pintype "bidirectional"))
    )
    (net (code "99") (name "unconnected-(IC1-PA2(ADCA2)-Pad97)") (class "Default")
      (node (ref "IC1") (pin "97") (pinfunction "PA2(ADCA2)_97") (pintype "bidirectional"))
    )
    (net (code "100") (name "unconnected-(IC1-PA3(ADCA3)-Pad98)") (class "Default")
      (node (ref "IC1") (pin "98") (pinfunction "PA3(ADCA3)_98") (pintype "bidirectional"))
    )
    (net (code "101") (name "unconnected-(IC1-PA4(ADCA4)-Pad99)") (class "Default")
      (node (ref "IC1") (pin "99") (pinfunction "PA4(ADCA4)_99") (pintype "bidirectional"))
    )
    (net (code "102") (name "unconnected-(IC1-PA5(ADCA5)-Pad100)") (class "Default")
      (node (ref "IC1") (pin "100") (pinfunction "PA5(ADCA5)_100") (pintype "bidirectional"))
    )
    (net (code "103") (name "unconnected-(IC1-PA7{slash}(ADCA7{slash}AC0-OUT)-Pad2)") (class "Default")
      (node (ref "IC1") (pin "2") (pinfunction "PA7/(ADCA7/AC0-OUT)_2") (pintype "bidirectional"))
    )
    (net (code "104") (name "unconnected-(IC1-PB0(ADCB0{slash}AREFB)-Pad5)") (class "Default")
      (node (ref "IC1") (pin "5") (pinfunction "PB0(ADCB0/AREFB)_5") (pintype "bidirectional"))
    )
    (net (code "105") (name "unconnected-(IC1-PB1(ADCB1)-Pad6)") (class "Default")
      (node (ref "IC1") (pin "6") (pinfunction "PB1(ADCB1)_6") (pintype "bidirectional"))
    )
    (net (code "106") (name "unconnected-(IC1-PB2(ADCB2{slash}DAC0)-Pad7)") (class "Default")
      (node (ref "IC1") (pin "7") (pinfunction "PB2(ADCB2/DAC0)_7") (pintype "bidirectional"))
    )
    (net (code "107") (name "unconnected-(IC1-PB3(ADCB3{slash}DAC1)-Pad8)") (class "Default")
      (node (ref "IC1") (pin "8") (pinfunction "PB3(ADCB3/DAC1)_8") (pintype "bidirectional"))
    )
    (net (code "108") (name "unconnected-(IC1-PB4(ADCB4{slash}TMS)-Pad9)") (class "Default")
      (node (ref "IC1") (pin "9") (pinfunction "PB4(ADCB4/TMS)_9") (pintype "bidirectional"))
    )
    (net (code "109") (name "unconnected-(IC1-PB5(ADCB5{slash}TDI)-Pad10)") (class "Default")
      (node (ref "IC1") (pin "10") (pinfunction "PB5(ADCB5/TDI)_10") (pintype "bidirectional"))
    )
    (net (code "110") (name "unconnected-(IC1-PB6(ADCB6{slash}TCK)-Pad11)") (class "Default")
      (node (ref "IC1") (pin "11") (pinfunction "PB6(ADCB6/TCK)_11") (pintype "bidirectional"))
    )
    (net (code "111") (name "unconnected-(IC1-PB7(ADCB7{slash}AC0-OUT{slash}TDO)-Pad12)") (class "Default")
      (node (ref "IC1") (pin "12") (pinfunction "PB7(ADCB7/AC0-OUT/TDO)_12") (pintype "bidirectional"))
    )
    (net (code "112") (name "unconnected-(IC1-PC0(OC0A{slash}SDA)-Pad15)") (class "Default")
      (node (ref "IC1") (pin "15") (pinfunction "PC0(OC0A/SDA)_15") (pintype "bidirectional"))
    )
    (net (code "113") (name "unconnected-(IC1-PC1(OC0B{slash}XCK0{slash}SCL)-Pad16)") (class "Default")
      (node (ref "IC1") (pin "16") (pinfunction "PC1(OC0B/XCK0/SCL)_16") (pintype "bidirectional"))
    )
    (net (code "114") (name "unconnected-(IC1-PC2(OC0C{slash}RXD0)-Pad17)") (class "Default")
      (node (ref "IC1") (pin "17") (pinfunction "PC2(OC0C/RXD0)_17") (pintype "bidirectional"))
    )
    (net (code "115") (name "unconnected-(IC1-PC3(OC0D{slash}TXD0)-Pad18)") (class "Default")
      (node (ref "IC1") (pin "18") (pinfunction "PC3(OC0D/TXD0)_18") (pintype "bidirectional"))
    )
    (net (code "116") (name "unconnected-(IC1-PC4(OC1A{slash}~{SS})-Pad19)") (class "Default")
      (node (ref "IC1") (pin "19") (pinfunction "PC4(OC1A/~{SS})_19") (pintype "bidirectional"))
    )
    (net (code "117") (name "unconnected-(IC1-PC5(OC1B{slash}MOSI{slash}XCK1)-Pad20)") (class "Default")
      (node (ref "IC1") (pin "20") (pinfunction "PC5(OC1B/MOSI/XCK1)_20") (pintype "bidirectional"))
    )
    (net (code "118") (name "unconnected-(IC1-PE2(OC0C{slash}RXD0)-Pad37)") (class "Default")
      (node (ref "IC1") (pin "37") (pinfunction "PE2(OC0C/RXD0)_37") (pintype "bidirectional"))
    )
    (net (code "119") (name "unconnected-(IC1-PE3(OC0D{slash}TXD0)-Pad38)") (class "Default")
      (node (ref "IC1") (pin "38") (pinfunction "PE3(OC0D/TXD0)_38") (pintype "bidirectional"))
    )
    (net (code "120") (name "unconnected-(IC1-PE4(OC1A{slash}~{SS})-Pad39)") (class "Default")
      (node (ref "IC1") (pin "39") (pinfunction "PE4(OC1A/~{SS})_39") (pintype "bidirectional"))
    )
    (net (code "121") (name "unconnected-(IC1-PE5(OC1B{slash}XCK1{slash}MOSI)-Pad40)") (class "Default")
      (node (ref "IC1") (pin "40") (pinfunction "PE5(OC1B/XCK1/MOSI)_40") (pintype "bidirectional"))
    )
    (net (code "122") (name "unconnected-(IC1-PE6(RSC1{slash}MISO{slash}TOSC2)-Pad41)") (class "Default")
      (node (ref "IC1") (pin "41") (pinfunction "PE6(RSC1/MISO/TOSC2)_41") (pintype "bidirectional"))
    )
    (net (code "123") (name "unconnected-(IC1-PE7(TSD1{slash}SCK{slash}CLKO{slash}EVO{slash}TOSC1)-Pad42)") (class "Default")
      (node (ref "IC1") (pin "42") (pinfunction "PE7(TSD1/SCK/CLKO/EVO/TOSC1)_42") (pintype "bidirectional"))
    )
    (net (code "124") (name "unconnected-(IC1-PF0(OC0A{slash}SDA)-Pad45)") (class "Default")
      (node (ref "IC1") (pin "45") (pinfunction "PF0(OC0A/SDA)_45") (pintype "bidirectional"))
    )
    (net (code "125") (name "unconnected-(IC1-PF1(OC0B{slash}XCK0{slash}SCL)-Pad46)") (class "Default")
      (node (ref "IC1") (pin "46") (pinfunction "PF1(OC0B/XCK0/SCL)_46") (pintype "bidirectional"))
    )
    (net (code "126") (name "unconnected-(IC1-PF4(OC1A{slash}~{SS})-Pad49)") (class "Default")
      (node (ref "IC1") (pin "49") (pinfunction "PF4(OC1A/~{SS})_49") (pintype "bidirectional"))
    )
    (net (code "127") (name "unconnected-(IC1-PF5(OC1B{slash}XCK1{slash}MOSI)-Pad50)") (class "Default")
      (node (ref "IC1") (pin "50") (pinfunction "PF5(OC1B/XCK1/MOSI)_50") (pintype "bidirectional"))
    )
    (net (code "128") (name "unconnected-(IC1-PF6(RXD1{slash}MISO)-Pad51)") (class "Default")
      (node (ref "IC1") (pin "51") (pinfunction "PF6(RXD1/MISO)_51") (pintype "bidirectional"))
    )
    (net (code "129") (name "unconnected-(IC1-PF7(TXD1{slash}SCK)-Pad52)") (class "Default")
      (node (ref "IC1") (pin "52") (pinfunction "PF7(TXD1/SCK)_52") (pintype "bidirectional"))
    )
    (net (code "130") (name "unconnected-(IC1-PJ3(D3{slash}A3{slash}A11)-Pad68)") (class "Default")
      (node (ref "IC1") (pin "68") (pinfunction "PJ3(D3/A3/A11)_68") (pintype "bidirectional"))
    )
    (net (code "131") (name "unconnected-(IC1-PJ4(A8{slash}D4{slash}A4{slash}A12)-Pad69)") (class "Default")
      (node (ref "IC1") (pin "69") (pinfunction "PJ4(A8/D4/A4/A12)_69") (pintype "bidirectional"))
    )
    (net (code "132") (name "unconnected-(IC1-PJ5(A9{slash}D5{slash}A5{slash}A13)-Pad70)") (class "Default")
      (node (ref "IC1") (pin "70") (pinfunction "PJ5(A9/D5/A5/A13)_70") (pintype "bidirectional"))
    )
    (net (code "133") (name "unconnected-(IC1-PJ7(A11{slash}D7{slash}A7{slash}A15)-Pad72)") (class "Default")
      (node (ref "IC1") (pin "72") (pinfunction "PJ7(A11/D7/A7/A15)_72") (pintype "bidirectional"))
    )
    (net (code "134") (name "unconnected-(IC1-PK1(A1{slash}A9{slash}A17)-Pad76)") (class "Default")
      (node (ref "IC1") (pin "76") (pinfunction "PK1(A1/A9/A17)_76") (pintype "bidirectional"))
    )
    (net (code "135") (name "unconnected-(IC1-PK2(A2{slash}A10{slash}A18)-Pad77)") (class "Default")
      (node (ref "IC1") (pin "77") (pinfunction "PK2(A2/A10/A18)_77") (pintype "bidirectional"))
    )
    (net (code "136") (name "unconnected-(IC1-PK3(A3{slash}A11{slash}A19)-Pad78)") (class "Default")
      (node (ref "IC1") (pin "78") (pinfunction "PK3(A3/A11/A19)_78") (pintype "bidirectional"))
    )
    (net (code "137") (name "unconnected-(IC1-PK4(A4{slash}A12{slash}A20)-Pad79)") (class "Default")
      (node (ref "IC1") (pin "79") (pinfunction "PK4(A4/A12/A20)_79") (pintype "bidirectional"))
    )
    (net (code "138") (name "unconnected-(IC1-PK5(A5{slash}A13{slash}A22)-Pad80)") (class "Default")
      (node (ref "IC1") (pin "80") (pinfunction "PK5(A5/A13/A22)_80") (pintype "bidirectional"))
    )
    (net (code "139") (name "unconnected-(IC1-PK6(A6{slash}A14{slash}A22)-Pad81)") (class "Default")
      (node (ref "IC1") (pin "81") (pinfunction "PK6(A6/A14/A22)_81") (pintype "bidirectional"))
    )
    (net (code "140") (name "unconnected-(IC1-PK7(A7{slash}A15{slash}A23)-Pad82)") (class "Default")
      (node (ref "IC1") (pin "82") (pinfunction "PK7(A7/A15/A23)_82") (pintype "bidirectional"))
    )
    (net (code "141") (name "unconnected-(IC1-PQ0(TOSC1)-Pad85)") (class "Default")
      (node (ref "IC1") (pin "85") (pinfunction "PQ0(TOSC1)_85") (pintype "bidirectional"))
    )
    (net (code "142") (name "unconnected-(IC1-PQ1(TOSC2)-Pad86)") (class "Default")
      (node (ref "IC1") (pin "86") (pinfunction "PQ1(TOSC2)_86") (pintype "bidirectional"))
    )
    (net (code "143") (name "unconnected-(IC1-PQ2-Pad87)") (class "Default")
      (node (ref "IC1") (pin "87") (pinfunction "PQ2_87") (pintype "bidirectional"))
    )
    (net (code "144") (name "unconnected-(IC1-PQ3-Pad88)") (class "Default")
      (node (ref "IC1") (pin "88") (pinfunction "PQ3_88") (pintype "bidirectional"))
    )
    (net (code "145") (name "unconnected-(IC1-PR0(XTAL2)-Pad91)") (class "Default")
      (node (ref "IC1") (pin "91") (pinfunction "PR0(XTAL2)_91") (pintype "bidirectional"))
    )
    (net (code "146") (name "unconnected-(IC3-CBUS0-Pad23)") (class "Default")
      (node (ref "IC3") (pin "23") (pinfunction "CBUS0_23") (pintype "bidirectional"))
    )
    (net (code "147") (name "unconnected-(IC3-CBUS1-Pad22)") (class "Default")
      (node (ref "IC3") (pin "22") (pinfunction "CBUS1_22") (pintype "bidirectional"))
    )
    (net (code "148") (name "unconnected-(IC3-CBUS2-Pad13)") (class "Default")
      (node (ref "IC3") (pin "13") (pinfunction "CBUS2_13") (pintype "bidirectional"))
    )
    (net (code "149") (name "unconnected-(IC3-CBUS3-Pad14)") (class "Default")
      (node (ref "IC3") (pin "14") (pinfunction "CBUS3_14") (pintype "bidirectional"))
    )
    (net (code "150") (name "unconnected-(IC3-CBUS4-Pad12)") (class "Default")
      (node (ref "IC3") (pin "12") (pinfunction "CBUS4_12") (pintype "bidirectional"))
    )
    (net (code "151") (name "unconnected-(IC3-OSCI-Pad27)") (class "Default")
      (node (ref "IC3") (pin "27") (pinfunction "OSCI_27") (pintype "input"))
    )
    (net (code "152") (name "unconnected-(IC3-OSCO-Pad28)") (class "Default")
      (node (ref "IC3") (pin "28") (pinfunction "OSCO_28") (pintype "output"))
    )
    (net (code "153") (name "unconnected-(IC3-~{DCD}-Pad10)") (class "Default")
      (node (ref "IC3") (pin "10") (pinfunction "~{DCD}_10") (pintype "input"))
    )
    (net (code "154") (name "unconnected-(IC3-~{DSR}-Pad9)") (class "Default")
      (node (ref "IC3") (pin "9") (pinfunction "~{DSR}_9") (pintype "input"))
    )
    (net (code "155") (name "unconnected-(IC3-~{DTR}-Pad2)") (class "Default")
      (node (ref "IC3") (pin "2") (pinfunction "~{DTR}_2") (pintype "output"))
    )
    (net (code "156") (name "unconnected-(IC3-~{RESET}-Pad19)") (class "Default")
      (node (ref "IC3") (pin "19") (pinfunction "~{RESET}_19") (pintype "input"))
    )
    (net (code "157") (name "unconnected-(IC3-~{RI}-Pad6)") (class "Default")
      (node (ref "IC3") (pin "6") (pinfunction "~{RI}_6") (pintype "input"))
    )
    (net (code "158") (name "unconnected-(IC4-N{slash}C-Pad4)") (class "Default")
      (node (ref "IC4") (pin "4") (pinfunction "N/C_4") (pintype "bidirectional"))
    )
    (net (code "159") (name "unconnected-(IC5-N{slash}C-Pad4)") (class "Default")
      (node (ref "IC5") (pin "4") (pinfunction "N/C_4") (pintype "bidirectional"))
    )
    (net (code "160") (name "unconnected-(IC6-AVDD{slash}NC-Pad3)") (class "Default")
      (node (ref "IC6") (pin "3") (pinfunction "AVDD/NC_3") (pintype "bidirectional"))
    )
    (net (code "161") (name "unconnected-(IC6-BGND{slash}NC-Pad7)") (class "Default")
      (node (ref "IC6") (pin "7") (pinfunction "BGND/NC_7") (pintype "bidirectional"))
    )
    (net (code "162") (name "unconnected-(OSC-STANDBY#-PadP$1)") (class "Default")
      (node (ref "OSC") (pin "P$1") (pinfunction "STANDBY#_P$1") (pintype "passive"))
    )
    (net (code "163") (name "unconnected-(PDI-Pad3)") (class "Default")
      (node (ref "PDI") (pin "3") (pinfunction "3_3") (pintype "passive"))
    )
    (net (code "164") (name "unconnected-(PDI-Pad4)") (class "Default")
      (node (ref "PDI") (pin "4") (pinfunction "4_4") (pintype "passive"))
    )
    (net (code "165") (name "unconnected-(USB-4-PadP$4)") (class "Default")
      (node (ref "USB") (pin "P$4") (pinfunction "4_P$4") (pintype "bidirectional"))
    )
    (net (code "166") (name "unconnected-(USB-P$2-PadSHIELD_2)") (class "Default")
      (node (ref "USB") (pin "SHIELD_2") (pinfunction "P$2_SHIELD_2") (pintype "bidirectional"))
    )
    (net (code "167") (name "unconnected-(USB-P$3-PadSHIELD_3)") (class "Default")
      (node (ref "USB") (pin "SHIELD_3") (pinfunction "P$3_SHIELD_3") (pintype "bidirectional"))
    )
  )
)
